# mainBoard_New_3-21_v10.net
KiCad netlist of a schematic drawn in EAGLE
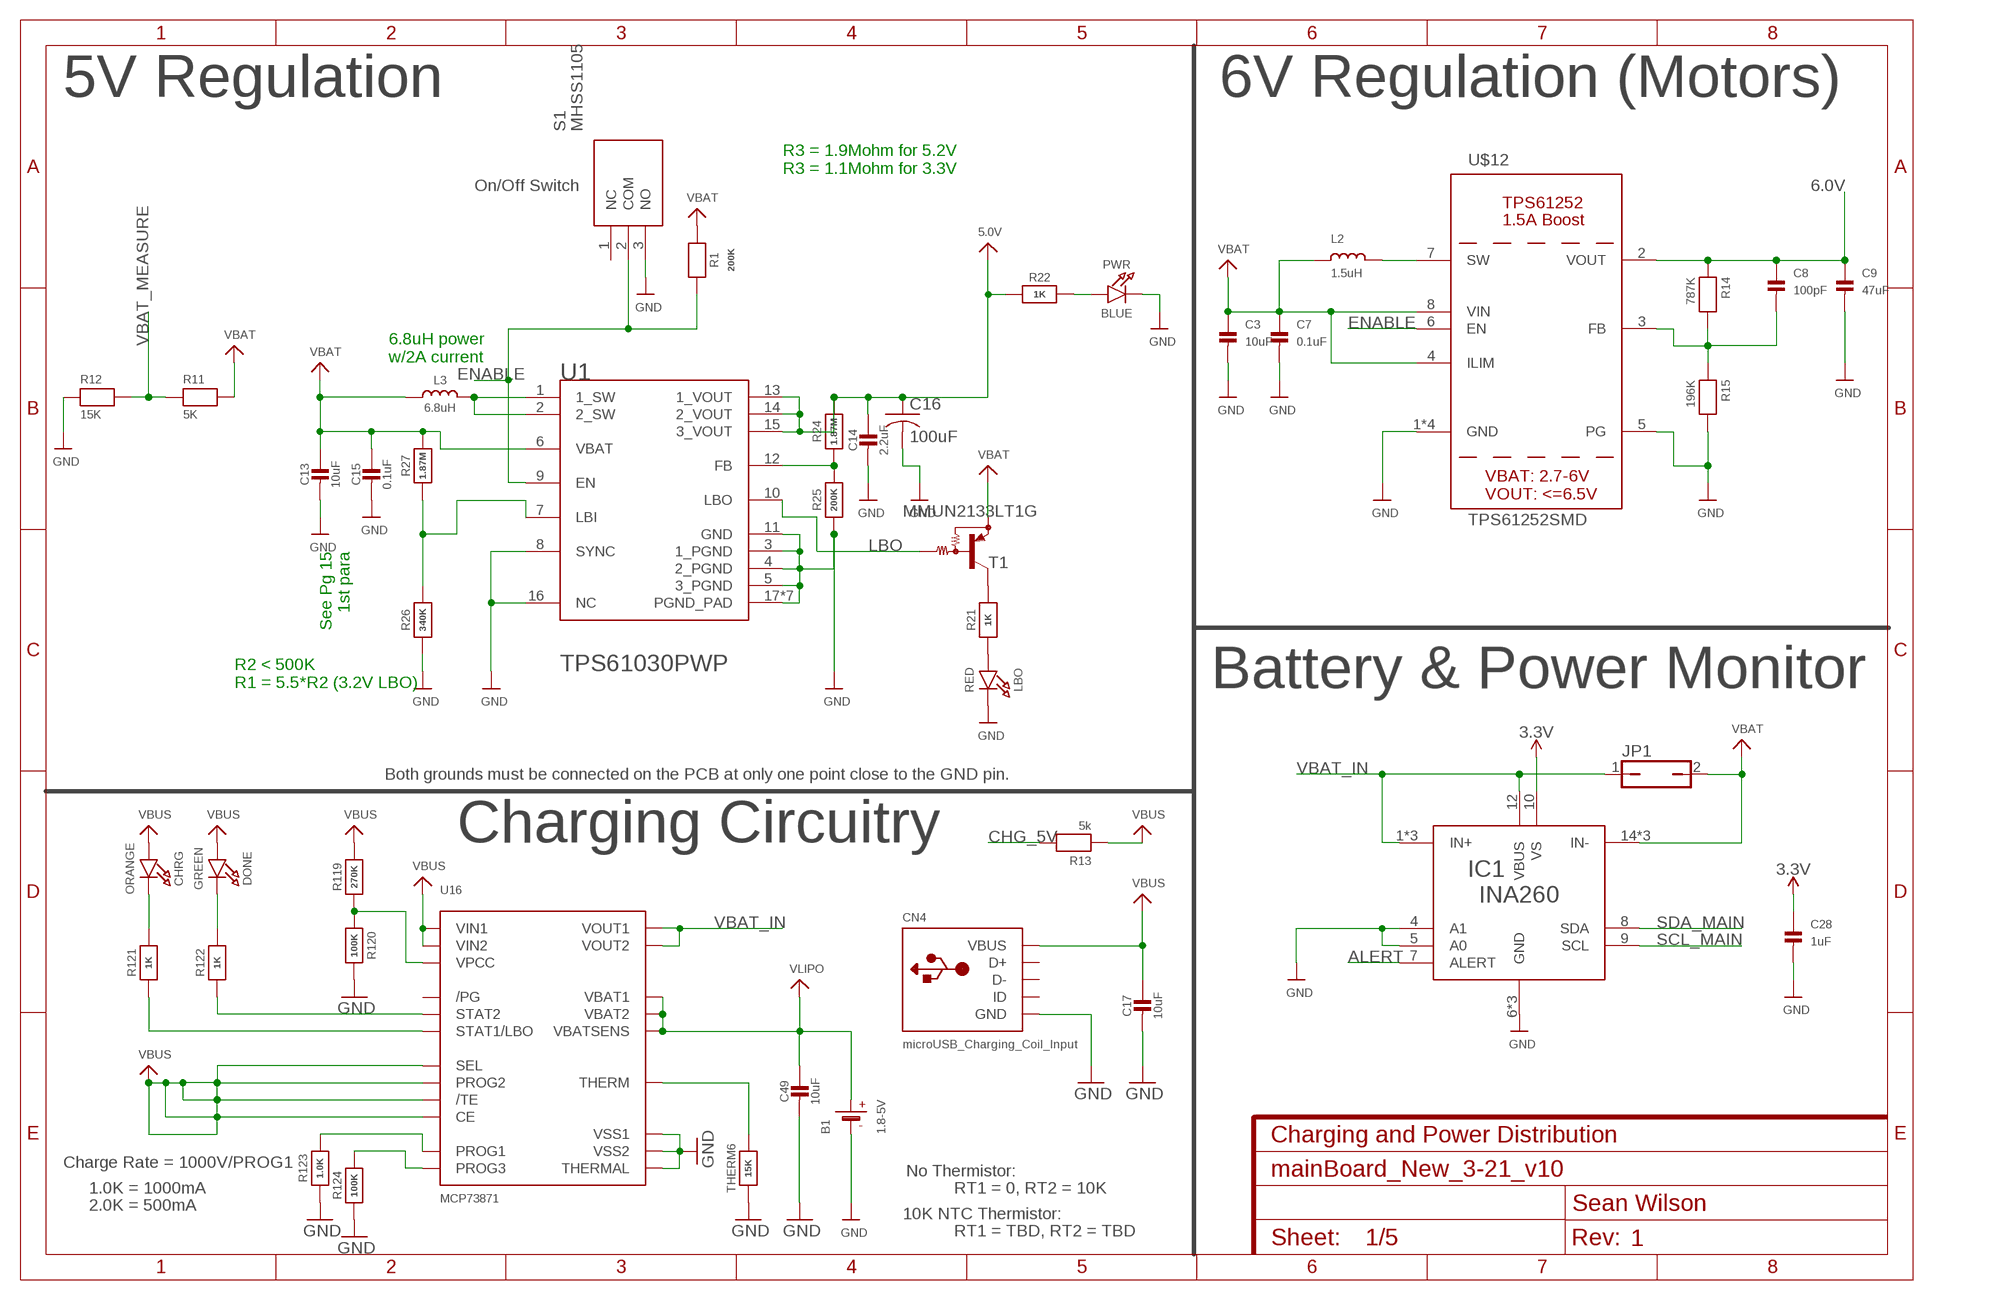
[diagram p0: schematic, sheet 1]
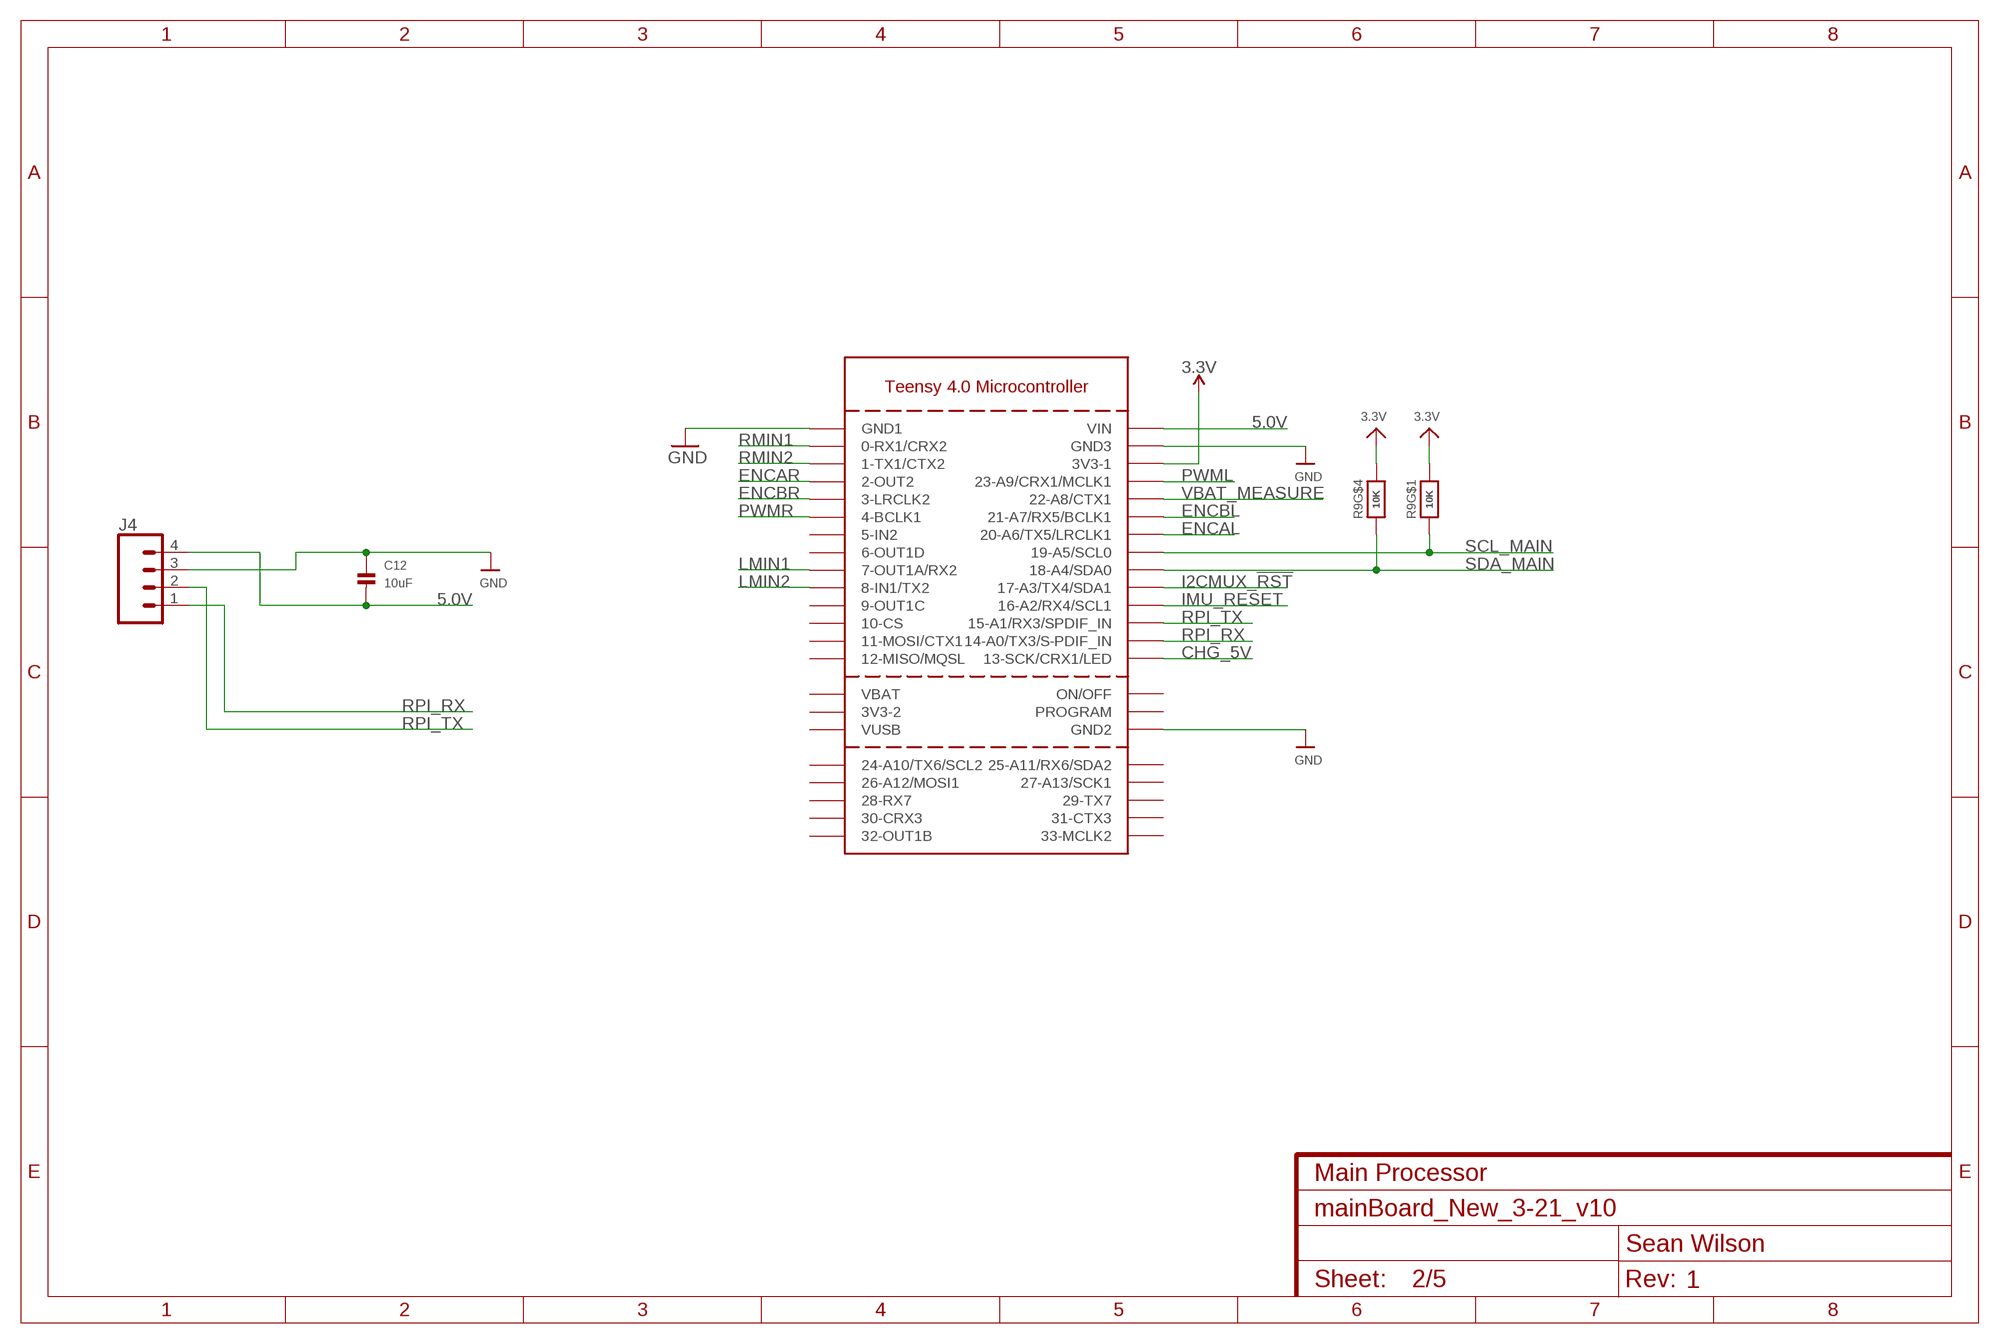
[diagram p1: schematic, sheet 2]
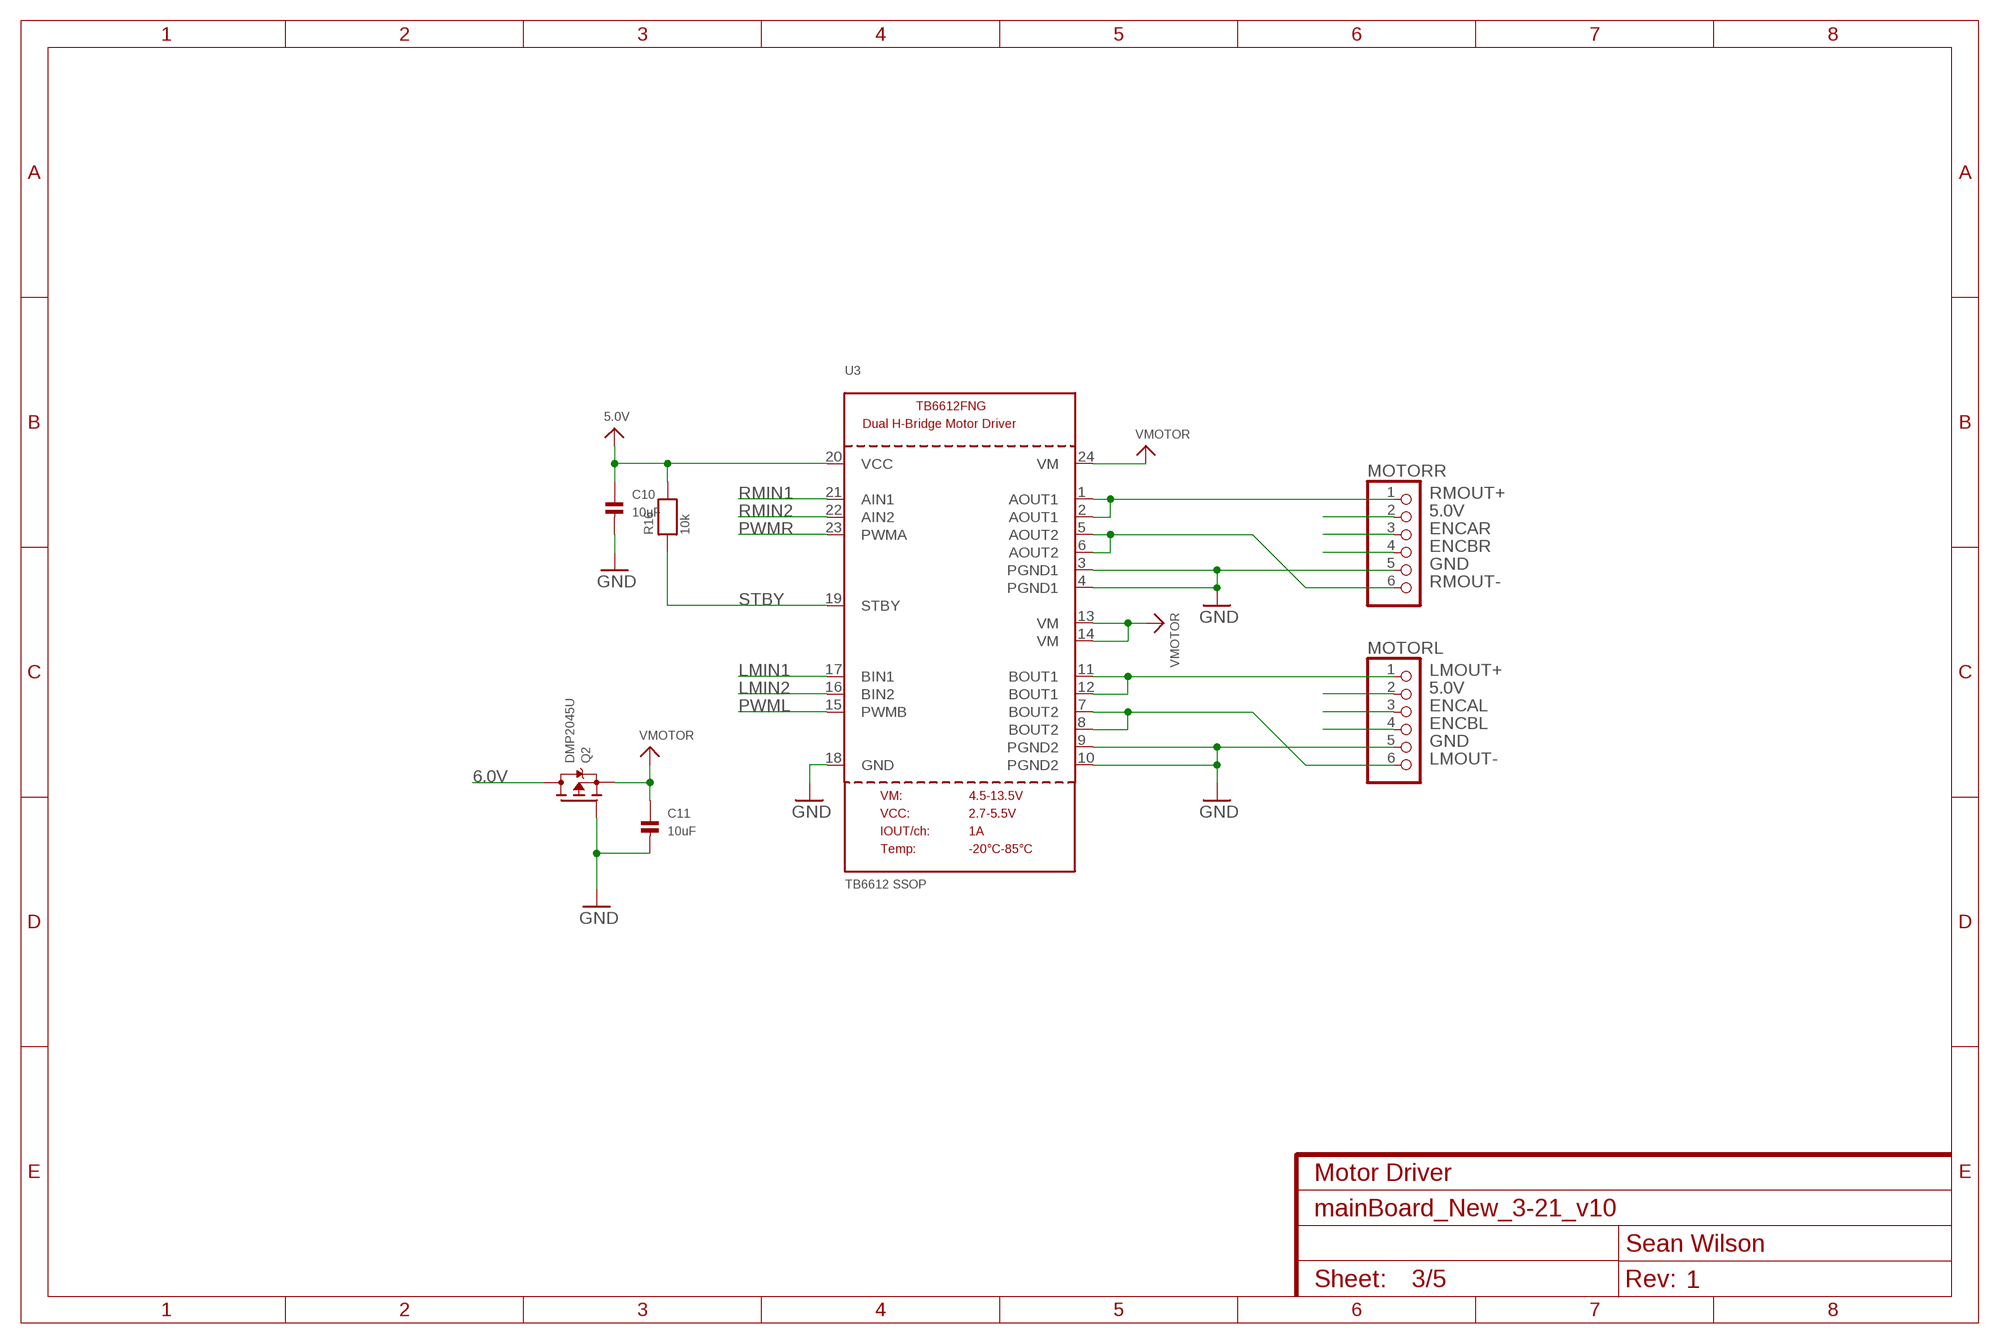
[diagram p2: schematic, sheet 3]
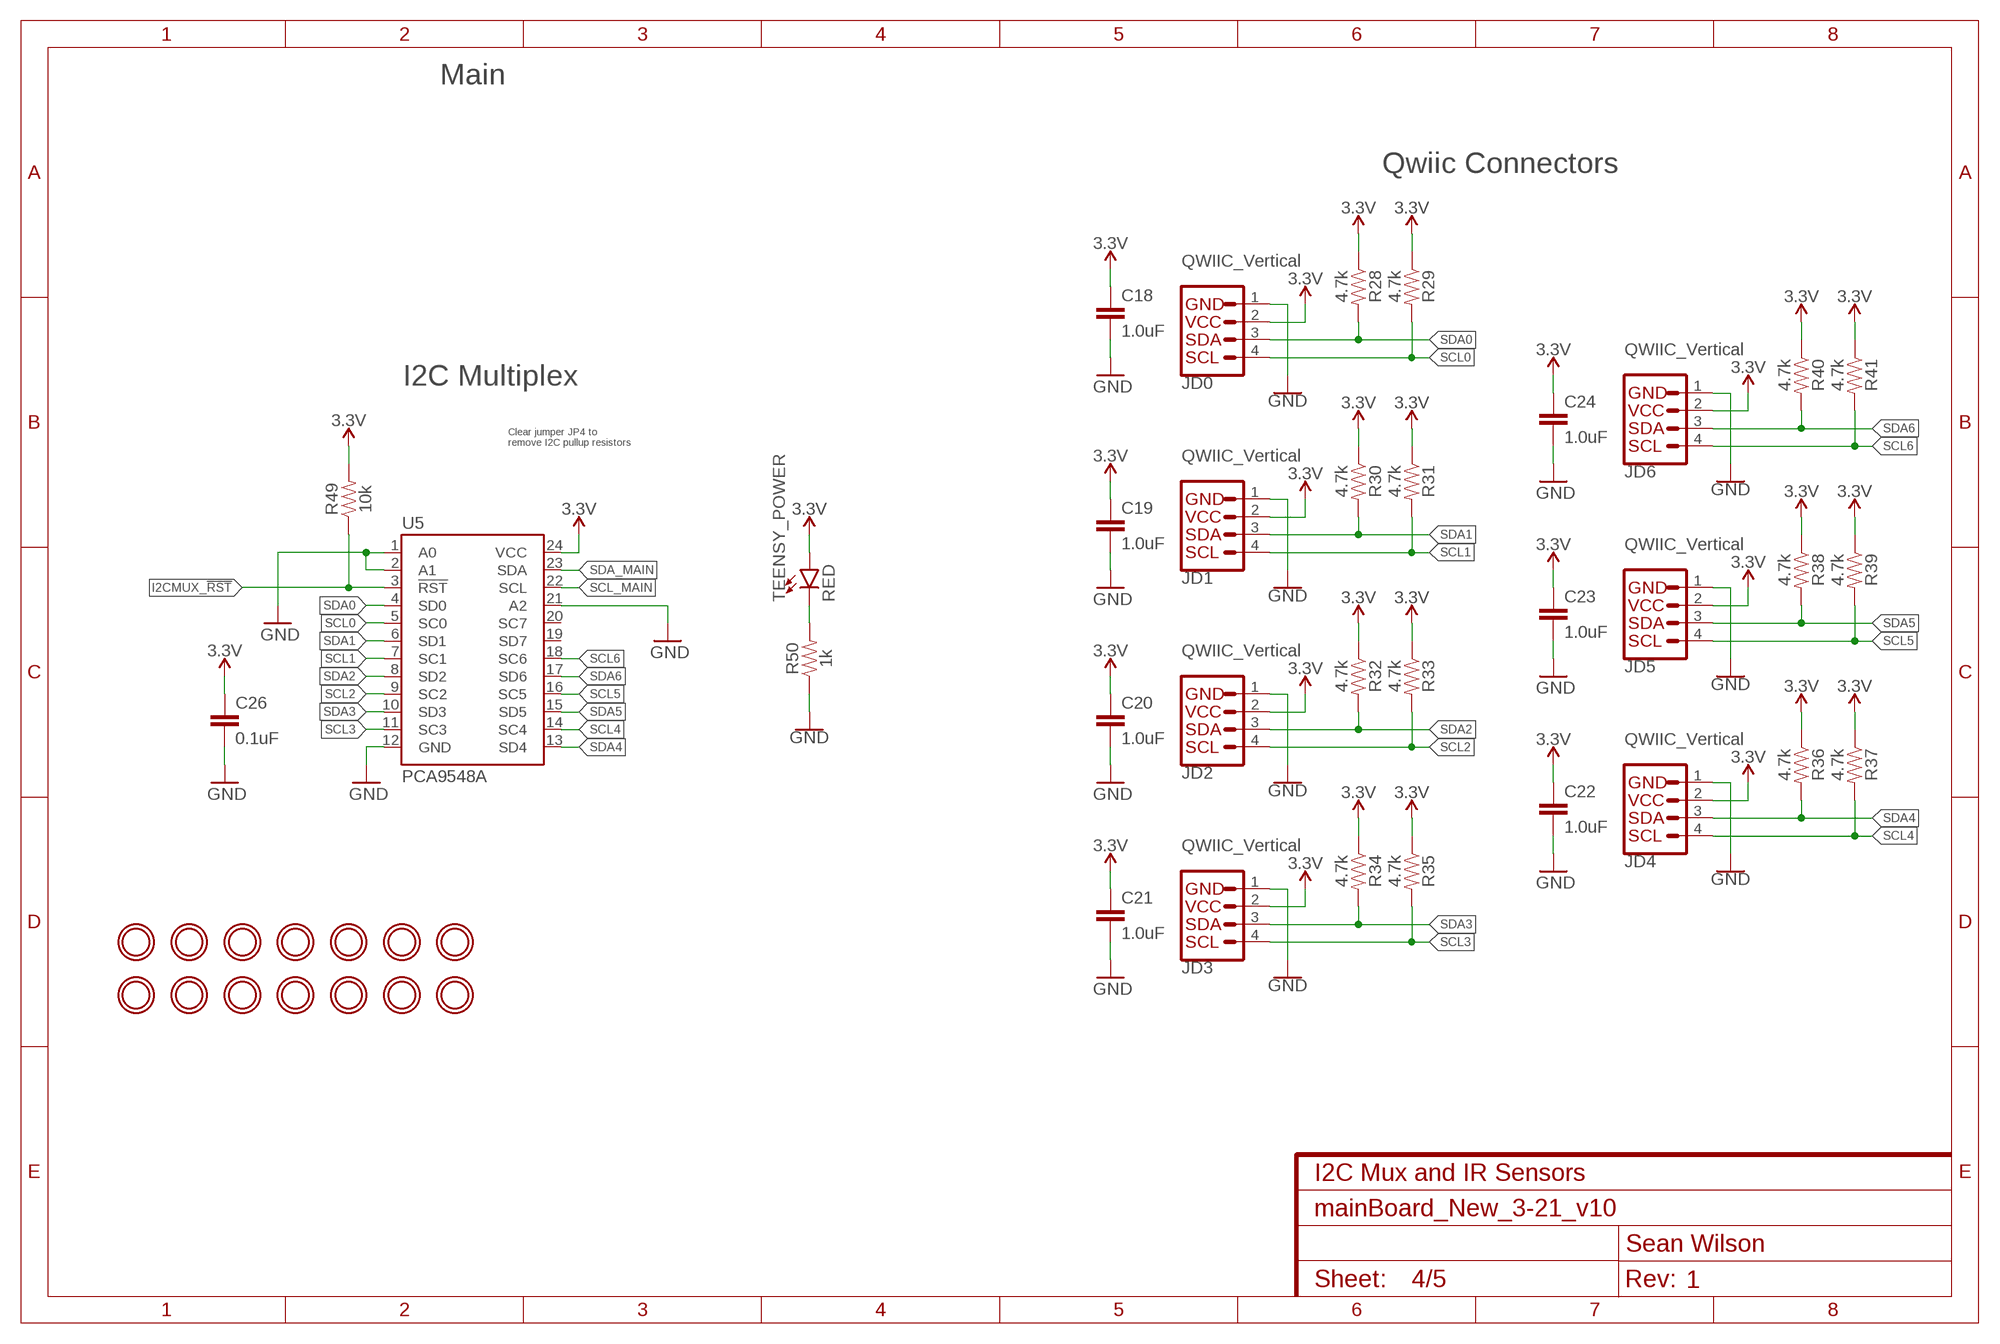
[diagram p3: schematic, sheet 4]
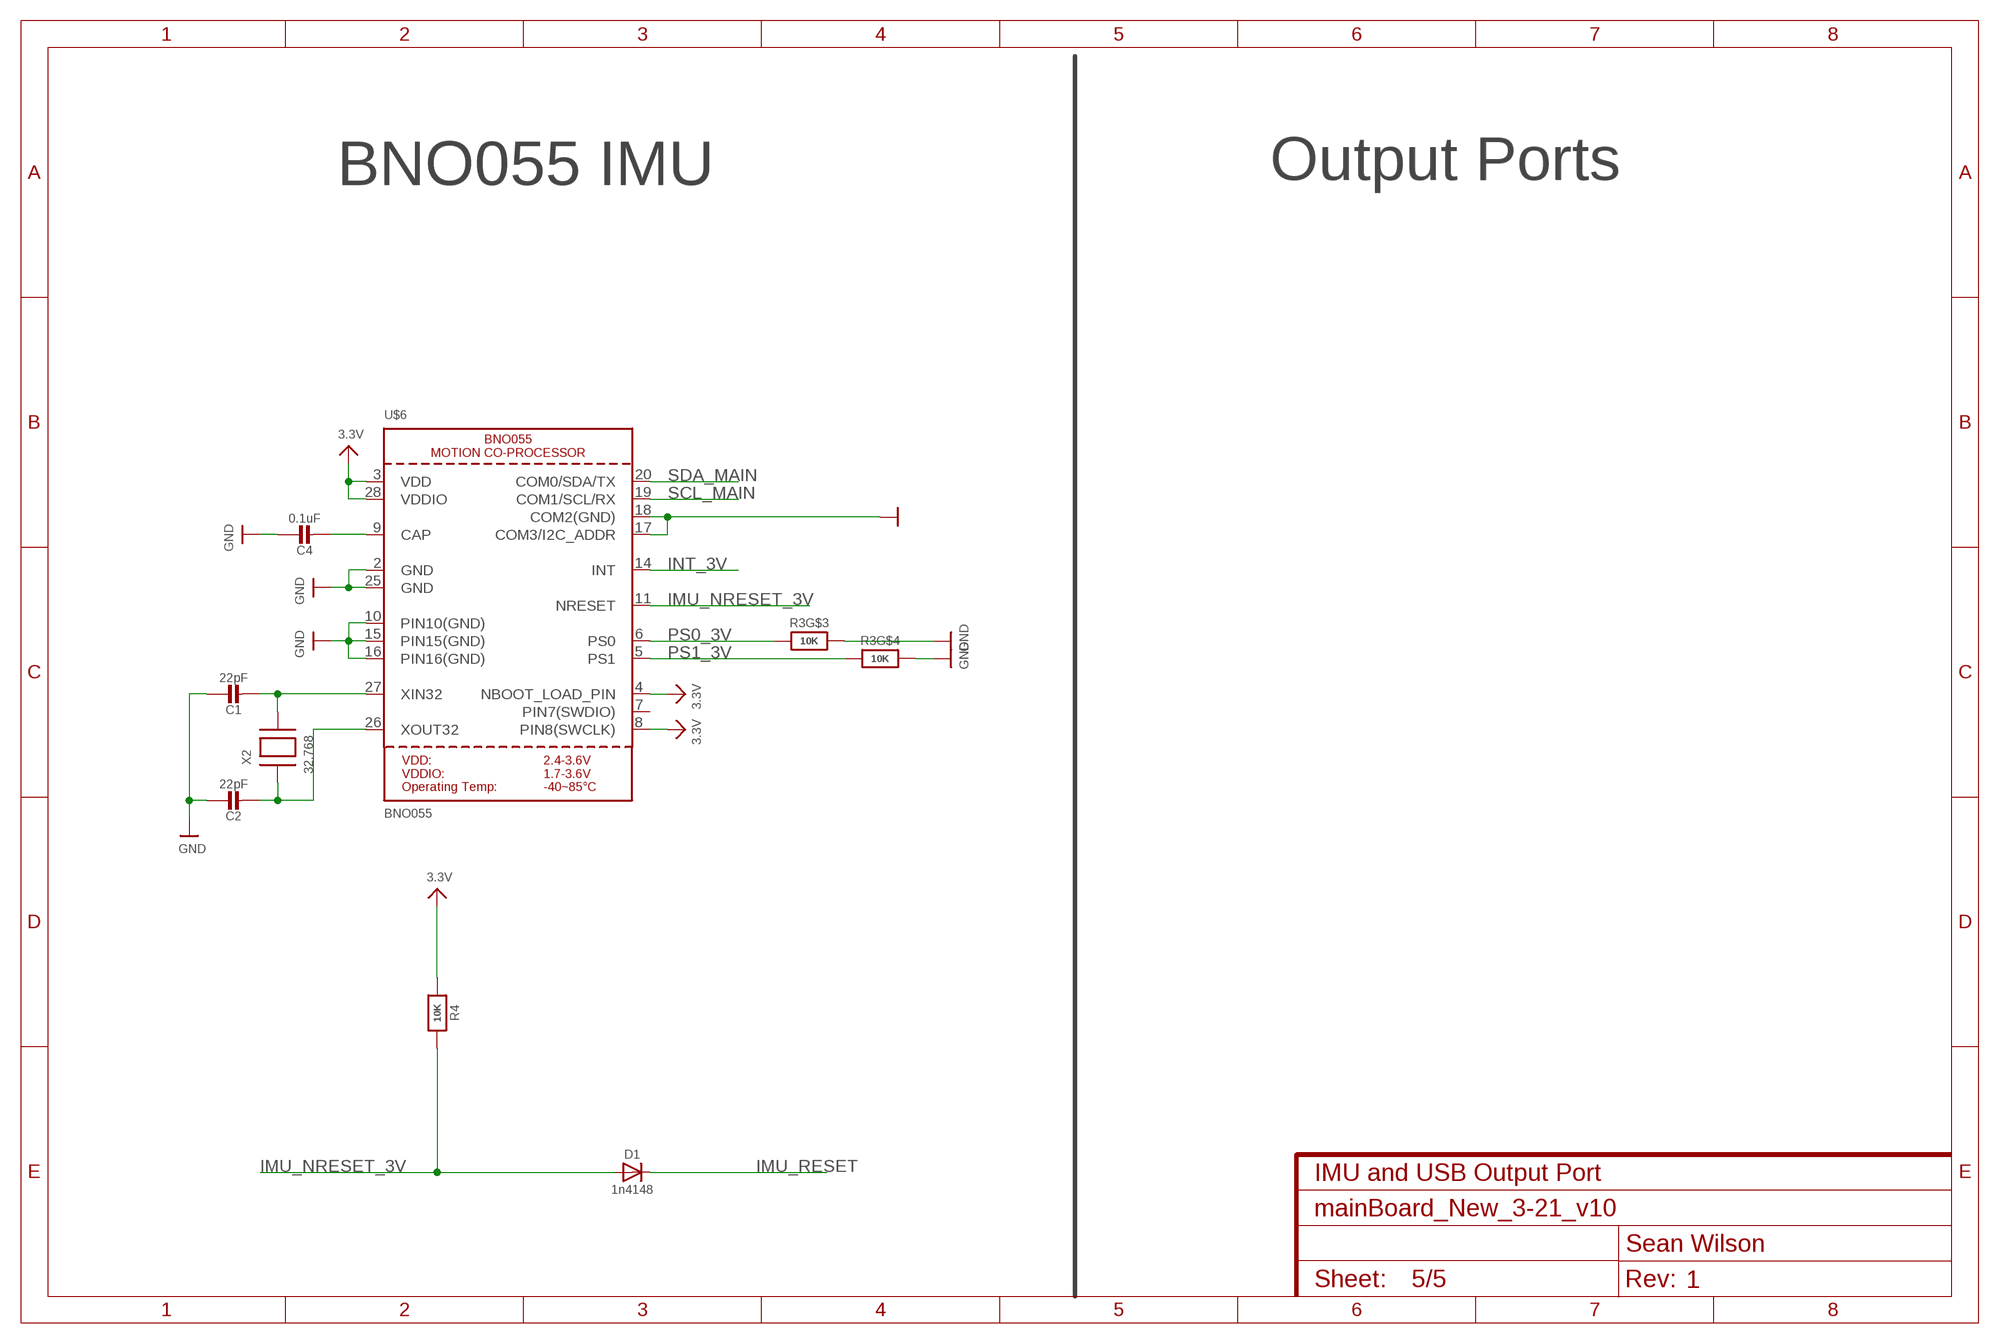
[diagram p4: schematic, sheet 5]

(export (version "E")
  (design (tool "Eeschema 10.0.6"))
  (components
    (comp (ref "C12")
      (value "10uF")
      (footprint "eagle-import:0603")
      (libsource (lib "eagle-import") (part "CAP_CERAMIC0603"))
    )
    (comp (ref "J4")
      (value "CONN_041X04_NO_SILK")
      (footprint "eagle-import:1X04_NO_SILK")
      (libsource (lib "eagle-import") (part "CONN_041X04_NO_SILK"))
    )
    (comp (ref "R9")
      (value "10K")
      (footprint "eagle-import:RESPACK_4X0603")
      (libsource (lib "eagle-import") (part "RESISTOR_4PACK"))
    )
    (comp (ref "U$57")
      (value "TEENSY40")
      (footprint "eagle-import:TEENSY40")
      (libsource (lib "eagle-import") (part "TEENSY40"))
    )
    (comp (ref "C10")
      (value "10uF")
      (footprint "eagle-import:0603")
      (libsource (lib "eagle-import") (part "CAP_CERAMIC0603"))
    )
    (comp (ref "C11")
      (value "10uF")
      (footprint "eagle-import:0603")
      (libsource (lib "eagle-import") (part "CAP_CERAMIC0603"))
    )
    (comp (ref "MOTORL")
      (value "PINHD-1X6CB")
      (footprint "eagle-import:1X06-CLEANBIG")
      (libsource (lib "eagle-import") (part "PINHD-1X6CB"))
    )
    (comp (ref "MOTORR")
      (value "PINHD-1X6CB")
      (footprint "eagle-import:1X06-CLEANBIG")
      (libsource (lib "eagle-import") (part "PINHD-1X6CB"))
    )
    (comp (ref "Q2")
      (value "DMP2045U")
      (footprint "eagle-import:SOT23-WIDE")
      (libsource (lib "eagle-import") (part "MOSFET-PWIDE"))
    )
    (comp (ref "R16")
      (value "10k")
      (footprint "eagle-import:0805")
      (libsource (lib "eagle-import") (part "RESISTOR0805"))
    )
    (comp (ref "U3")
      (value "TB6612 SSOP")
      (footprint "eagle-import:SSOP24")
      (libsource (lib "eagle-import") (part "TB6612FNGSSOP"))
    )
    (comp (ref "C1")
      (value "22pF")
      (footprint "eagle-import:0603-NO")
      (libsource (lib "eagle-import") (part "CAP_CERAMIC0603_NO"))
    )
    (comp (ref "C2")
      (value "22pF")
      (footprint "eagle-import:0603-NO")
      (libsource (lib "eagle-import") (part "CAP_CERAMIC0603_NO"))
    )
    (comp (ref "C4")
      (value "0.1uF")
      (footprint "eagle-import:0603-NO")
      (libsource (lib "eagle-import") (part "CAP_CERAMIC0603_NO"))
    )
    (comp (ref "D1")
      (value "1n4148")
      (footprint "eagle-import:SOD-323")
      (libsource (lib "eagle-import") (part "DIODESOD-323"))
    )
    (comp (ref "R3")
      (value "10K")
      (footprint "eagle-import:RESPACK_4X0603")
      (libsource (lib "eagle-import") (part "RESISTOR_4PACK"))
    )
    (comp (ref "R4")
      (value "10K")
      (footprint "eagle-import:0603-NO")
      (libsource (lib "eagle-import") (part "RESISTOR_0603_NOOUT"))
    )
    (comp (ref "U$6")
      (value "BNO055")
      (footprint "eagle-import:BNO055")
      (libsource (lib "eagle-import") (part "BNO055"))
    )
    (comp (ref "X2")
      (value "32.768")
      (footprint "eagle-import:XTAL3215")
      (libsource (lib "eagle-import") (part "XTAL-3.2X1.5"))
    )
    (comp (ref "C18")
      (value "1.0uF")
      (footprint "eagle-import:0603")
      (libsource (lib "eagle-import") (part "1.0UF-0603-16V-10%"))
    )
    (comp (ref "C19")
      (value "1.0uF")
      (footprint "eagle-import:0603")
      (libsource (lib "eagle-import") (part "1.0UF-0603-16V-10%"))
    )
    (comp (ref "C20")
      (value "1.0uF")
      (footprint "eagle-import:0603")
      (libsource (lib "eagle-import") (part "1.0UF-0603-16V-10%"))
    )
    (comp (ref "C21")
      (value "1.0uF")
      (footprint "eagle-import:0603")
      (libsource (lib "eagle-import") (part "1.0UF-0603-16V-10%"))
    )
    (comp (ref "C22")
      (value "1.0uF")
      (footprint "eagle-import:0603")
      (libsource (lib "eagle-import") (part "1.0UF-0603-16V-10%"))
    )
    (comp (ref "C23")
      (value "1.0uF")
      (footprint "eagle-import:0603")
      (libsource (lib "eagle-import") (part "1.0UF-0603-16V-10%"))
    )
    (comp (ref "C24")
      (value "1.0uF")
      (footprint "eagle-import:0603")
      (libsource (lib "eagle-import") (part "1.0UF-0603-16V-10%"))
    )
    (comp (ref "C26")
      (value "0.1uF")
      (footprint "eagle-import:0603")
      (libsource (lib "eagle-import") (part "0.1UF-0603-25V-(+80/-20%)"))
    )
    (comp (ref "JD0")
      (value "QWIIC_Vertical")
      (footprint "eagle-import:JST04_1MM_VERT")
      (libsource (lib "eagle-import") (part "QWIIC_CONNECTOR"))
    )
    (comp (ref "JD1")
      (value "QWIIC_Vertical")
      (footprint "eagle-import:JST04_1MM_VERT")
      (libsource (lib "eagle-import") (part "QWIIC_CONNECTOR"))
    )
    (comp (ref "JD2")
      (value "QWIIC_Vertical")
      (footprint "eagle-import:JST04_1MM_VERT")
      (libsource (lib "eagle-import") (part "QWIIC_CONNECTOR"))
    )
    (comp (ref "JD3")
      (value "QWIIC_Vertical")
      (footprint "eagle-import:JST04_1MM_VERT")
      (libsource (lib "eagle-import") (part "QWIIC_CONNECTOR"))
    )
    (comp (ref "JD4")
      (value "QWIIC_Vertical")
      (footprint "eagle-import:JST04_1MM_VERT")
      (libsource (lib "eagle-import") (part "QWIIC_CONNECTOR"))
    )
    (comp (ref "JD5")
      (value "QWIIC_Vertical")
      (footprint "eagle-import:JST04_1MM_VERT")
      (libsource (lib "eagle-import") (part "QWIIC_CONNECTOR"))
    )
    (comp (ref "JD6")
      (value "QWIIC_Vertical")
      (footprint "eagle-import:JST04_1MM_VERT")
      (libsource (lib "eagle-import") (part "QWIIC_CONNECTOR"))
    )
    (comp (ref "R28")
      (value "4.7k")
      (footprint "eagle-import:0603")
      (libsource (lib "eagle-import") (part "4.7KOHM-0603-1/10W-1%"))
    )
    (comp (ref "R29")
      (value "4.7k")
      (footprint "eagle-import:0603")
      (libsource (lib "eagle-import") (part "4.7KOHM-0603-1/10W-1%"))
    )
    (comp (ref "R30")
      (value "4.7k")
      (footprint "eagle-import:0603")
      (libsource (lib "eagle-import") (part "4.7KOHM-0603-1/10W-1%"))
    )
    (comp (ref "R31")
      (value "4.7k")
      (footprint "eagle-import:0603")
      (libsource (lib "eagle-import") (part "4.7KOHM-0603-1/10W-1%"))
    )
    (comp (ref "R32")
      (value "4.7k")
      (footprint "eagle-import:0603")
      (libsource (lib "eagle-import") (part "4.7KOHM-0603-1/10W-1%"))
    )
    (comp (ref "R33")
      (value "4.7k")
      (footprint "eagle-import:0603")
      (libsource (lib "eagle-import") (part "4.7KOHM-0603-1/10W-1%"))
    )
    (comp (ref "R34")
      (value "4.7k")
      (footprint "eagle-import:0603")
      (libsource (lib "eagle-import") (part "4.7KOHM-0603-1/10W-1%"))
    )
    (comp (ref "R35")
      (value "4.7k")
      (footprint "eagle-import:0603")
      (libsource (lib "eagle-import") (part "4.7KOHM-0603-1/10W-1%"))
    )
    (comp (ref "R36")
      (value "4.7k")
      (footprint "eagle-import:0603")
      (libsource (lib "eagle-import") (part "4.7KOHM-0603-1/10W-1%"))
    )
    (comp (ref "R37")
      (value "4.7k")
      (footprint "eagle-import:0603")
      (libsource (lib "eagle-import") (part "4.7KOHM-0603-1/10W-1%"))
    )
    (comp (ref "R38")
      (value "4.7k")
      (footprint "eagle-import:0603")
      (libsource (lib "eagle-import") (part "4.7KOHM-0603-1/10W-1%"))
    )
    (comp (ref "R39")
      (value "4.7k")
      (footprint "eagle-import:0603")
      (libsource (lib "eagle-import") (part "4.7KOHM-0603-1/10W-1%"))
    )
    (comp (ref "R40")
      (value "4.7k")
      (footprint "eagle-import:0603")
      (libsource (lib "eagle-import") (part "4.7KOHM-0603-1/10W-1%"))
    )
    (comp (ref "R41")
      (value "4.7k")
      (footprint "eagle-import:0603")
      (libsource (lib "eagle-import") (part "4.7KOHM-0603-1/10W-1%"))
    )
    (comp (ref "R49")
      (value "10k")
      (footprint "eagle-import:0603")
      (libsource (lib "eagle-import") (part "10KOHM-0603-1/10W-1%"))
    )
    (comp (ref "R50")
      (value "1k")
      (footprint "eagle-import:0603")
      (libsource (lib "eagle-import") (part "1KOHM-0603-1/10W-1%"))
    )
    (comp (ref "TEENSY_POWER")
      (value "RED")
      (footprint "eagle-import:LED-0603")
      (libsource (lib "eagle-import") (part "LED-RED0603"))
    )
    (comp (ref "U$8")
      (value "MOUNTINGHOLE2.5")
      (footprint "eagle-import:MOUNTINGHOLE_2.5_PLATED")
      (libsource (lib "eagle-import") (part "MOUNTINGHOLE2.5"))
    )
    (comp (ref "U$30")
      (value "MOUNTINGHOLE2.5")
      (footprint "eagle-import:MOUNTINGHOLE_2.5_PLATED")
      (libsource (lib "eagle-import") (part "MOUNTINGHOLE2.5"))
    )
    (comp (ref "U$31")
      (value "MOUNTINGHOLE2.5")
      (footprint "eagle-import:MOUNTINGHOLE_2.5_PLATED")
      (libsource (lib "eagle-import") (part "MOUNTINGHOLE2.5"))
    )
    (comp (ref "U$32")
      (value "MOUNTINGHOLE2.5")
      (footprint "eagle-import:MOUNTINGHOLE_2.5_PLATED")
      (libsource (lib "eagle-import") (part "MOUNTINGHOLE2.5"))
    )
    (comp (ref "U$33")
      (value "MOUNTINGHOLE2.5")
      (footprint "eagle-import:MOUNTINGHOLE_2.5_PLATED")
      (libsource (lib "eagle-import") (part "MOUNTINGHOLE2.5"))
    )
    (comp (ref "U$34")
      (value "MOUNTINGHOLE2.5")
      (footprint "eagle-import:MOUNTINGHOLE_2.5_PLATED")
      (libsource (lib "eagle-import") (part "MOUNTINGHOLE2.5"))
    )
    (comp (ref "U$35")
      (value "MOUNTINGHOLE2.5")
      (footprint "eagle-import:MOUNTINGHOLE_2.5_PLATED")
      (libsource (lib "eagle-import") (part "MOUNTINGHOLE2.5"))
    )
    (comp (ref "U$36")
      (value "MOUNTINGHOLE2.5")
      (footprint "eagle-import:MOUNTINGHOLE_2.5_PLATED")
      (libsource (lib "eagle-import") (part "MOUNTINGHOLE2.5"))
    )
    (comp (ref "U$37")
      (value "MOUNTINGHOLE2.5")
      (footprint "eagle-import:MOUNTINGHOLE_2.5_PLATED")
      (libsource (lib "eagle-import") (part "MOUNTINGHOLE2.5"))
    )
    (comp (ref "U$43")
      (value "MOUNTINGHOLE2.5")
      (footprint "eagle-import:MOUNTINGHOLE_2.5_PLATED")
      (libsource (lib "eagle-import") (part "MOUNTINGHOLE2.5"))
    )
    (comp (ref "U$45")
      (value "MOUNTINGHOLE2.5")
      (footprint "eagle-import:MOUNTINGHOLE_2.5_PLATED")
      (libsource (lib "eagle-import") (part "MOUNTINGHOLE2.5"))
    )
    (comp (ref "U$46")
      (value "MOUNTINGHOLE2.5")
      (footprint "eagle-import:MOUNTINGHOLE_2.5_PLATED")
      (libsource (lib "eagle-import") (part "MOUNTINGHOLE2.5"))
    )
    (comp (ref "U$47")
      (value "MOUNTINGHOLE2.5")
      (footprint "eagle-import:MOUNTINGHOLE_2.5_PLATED")
      (libsource (lib "eagle-import") (part "MOUNTINGHOLE2.5"))
    )
    (comp (ref "U$48")
      (value "MOUNTINGHOLE2.5")
      (footprint "eagle-import:MOUNTINGHOLE_2.5_PLATED")
      (libsource (lib "eagle-import") (part "MOUNTINGHOLE2.5"))
    )
    (comp (ref "U5")
      (value "PCA9548A")
      (footprint "eagle-import:TSSOP28")
      (libsource (lib "eagle-import") (part "PCA9548A"))
    )
    (comp (ref "B1")
      (value "1.8-5V")
      (footprint "eagle-import:JSTPH2")
      (libsource (lib "eagle-import") (part "BATTERY"))
    )
    (comp (ref "C3")
      (value "10uF")
      (footprint "eagle-import:0603")
      (libsource (lib "eagle-import") (part "CAP_CERAMIC0603"))
    )
    (comp (ref "C7")
      (value "0.1uF")
      (footprint "eagle-import:0805")
      (libsource (lib "eagle-import") (part "CAP_CERAMIC0805"))
    )
    (comp (ref "C8")
      (value "100pF")
      (footprint "eagle-import:0603")
      (libsource (lib "eagle-import") (part "CAP_CERAMIC0603"))
    )
    (comp (ref "C9")
      (value "47uF")
      (footprint "eagle-import:1206")
      (libsource (lib "eagle-import") (part "CAP_CERAMIC1206"))
    )
    (comp (ref "C13")
      (value "10uF")
      (footprint "eagle-import:0805-NO")
      (libsource (lib "eagle-import") (part "CAP_CERAMIC0805-NOOUTLINE"))
    )
    (comp (ref "C14")
      (value "2.2uF")
      (footprint "eagle-import:0805-NO")
      (libsource (lib "eagle-import") (part "CAP_CERAMIC0805-NOOUTLINE"))
    )
    (comp (ref "C15")
      (value "0.1uF")
      (footprint "eagle-import:0805_10MGAP")
      (libsource (lib "eagle-import") (part "CAP_CERAMIC0805_10MGAP"))
    )
    (comp (ref "C16")
      (value "100uF")
      (footprint "eagle-import:C1210")
      (libsource (lib "eagle-import") (part "C-USC1210"))
    )
    (comp (ref "C17")
      (value "10uF")
      (footprint "eagle-import:0805-NO")
      (libsource (lib "eagle-import") (part "CAP_CERAMIC0805-NOOUTLINE"))
    )
    (comp (ref "C28")
      (value "1uF")
      (footprint "eagle-import:0603-NO")
      (libsource (lib "eagle-import") (part "CAP_CERAMIC0603_NO"))
    )
    (comp (ref "C49")
      (value "10uF")
      (footprint "eagle-import:0805-NO")
      (libsource (lib "eagle-import") (part "CAP_CERAMIC0805-NOOUTLINE"))
    )
    (comp (ref "CHRG")
      (value "ORANGE")
      (footprint "eagle-import:CHIPLED_0805_NOOUTLINE")
      (libsource (lib "eagle-import") (part "LED0805_NOOUTLINE"))
    )
    (comp (ref "CN4")
      (value "microUSB_Charging_Coil_Input")
      (footprint "eagle-import:4UCONN_20329")
      (libsource (lib "eagle-import") (part "USBMICRO_20329"))
    )
    (comp (ref "DONE")
      (value "GREEN")
      (footprint "eagle-import:CHIPLED_0805_NOOUTLINE")
      (libsource (lib "eagle-import") (part "LED0805_NOOUTLINE"))
    )
    (comp (ref "IC1")
      (value "INA260")
      (footprint "eagle-import:TSSOP16")
      (libsource (lib "eagle-import") (part "INA260"))
    )
    (comp (ref "JP1")
      (value "JP1Q")
      (footprint "eagle-import:JP1")
      (libsource (lib "eagle-import") (part "JP1Q"))
    )
    (comp (ref "L2")
      (value "1.5uH")
      (footprint "eagle-import:MURATA_DFE252012P-1R5M=P2")
      (libsource (lib "eagle-import") (part "MURATA_DFE252012P-1R5M=P2"))
    )
    (comp (ref "L3")
      (value "6.8uH")
      (footprint "eagle-import:INDUCTOR_5X5MM_TDK_VLC5045")
      (libsource (lib "eagle-import") (part "INDUCTORTDK_VLC5045"))
    )
    (comp (ref "LBO")
      (value "RED")
      (footprint "eagle-import:CHIPLED_0805_NOOUTLINE")
      (libsource (lib "eagle-import") (part "LED0805_NOOUTLINE"))
    )
    (comp (ref "PWR")
      (value "BLUE")
      (footprint "eagle-import:CHIPLED_0805_NOOUTLINE")
      (libsource (lib "eagle-import") (part "LED0805_NOOUTLINE"))
    )
    (comp (ref "R1")
      (value "200K")
      (footprint "eagle-import:0805-NO")
      (libsource (lib "eagle-import") (part "RESISTOR0805_NOOUTLINE"))
    )
    (comp (ref "R11")
      (value "5K")
      (footprint "eagle-import:0805")
      (libsource (lib "eagle-import") (part "RESISTOR0805"))
    )
    (comp (ref "R12")
      (value "15K")
      (footprint "eagle-import:0805")
      (libsource (lib "eagle-import") (part "RESISTOR0805"))
    )
    (comp (ref "R13")
      (value "5k")
      (footprint "eagle-import:0805")
      (libsource (lib "eagle-import") (part "RESISTOR0805"))
    )
    (comp (ref "R14")
      (value "787K")
      (footprint "eagle-import:0805")
      (libsource (lib "eagle-import") (part "RESISTOR0805"))
    )
    (comp (ref "R15")
      (value "196K")
      (footprint "eagle-import:0805")
      (libsource (lib "eagle-import") (part "RESISTOR0805"))
    )
    (comp (ref "R21")
      (value "1K")
      (footprint "eagle-import:0805-NO")
      (libsource (lib "eagle-import") (part "RESISTOR0805_NOOUTLINE"))
    )
    (comp (ref "R22")
      (value "1K")
      (footprint "eagle-import:0805-NO")
      (libsource (lib "eagle-import") (part "RESISTOR0805_NOOUTLINE"))
    )
    (comp (ref "R24")
      (value "1.87M")
      (footprint "eagle-import:0805-NO")
      (libsource (lib "eagle-import") (part "RESISTOR0805_NOOUTLINE"))
    )
    (comp (ref "R25")
      (value "200K")
      (footprint "eagle-import:0805-NO")
      (libsource (lib "eagle-import") (part "RESISTOR0805_NOOUTLINE"))
    )
    (comp (ref "R26")
      (value "340K")
      (footprint "eagle-import:_0805MP")
      (libsource (lib "eagle-import") (part "microbuilder_vf.jQhFfLl6SwyupizEU6PNDA_RESISTOR_0805MP"))
    )
    (comp (ref "R27")
      (value "1.87M")
      (footprint "eagle-import:_0805MP")
      (libsource (lib "eagle-import") (part "microbuilder_vf.jQhFfLl6SwyupizEU6PNDA_RESISTOR_0805MP"))
    )
    (comp (ref "R119")
      (value "270K")
      (footprint "eagle-import:0805-NO")
      (libsource (lib "eagle-import") (part "RESISTOR0805_NOOUTLINE"))
    )
    (comp (ref "R120")
      (value "100K")
      (footprint "eagle-import:0805-NO")
      (libsource (lib "eagle-import") (part "RESISTOR0805_NOOUTLINE"))
    )
    (comp (ref "R121")
      (value "1K")
      (footprint "eagle-import:0805-NO")
      (libsource (lib "eagle-import") (part "RESISTOR0805_NOOUTLINE"))
    )
    (comp (ref "R122")
      (value "1K")
      (footprint "eagle-import:0805-NO")
      (libsource (lib "eagle-import") (part "RESISTOR0805_NOOUTLINE"))
    )
    (comp (ref "R123")
      (value "1.0K")
      (footprint "eagle-import:0805-NO")
      (libsource (lib "eagle-import") (part "RESISTOR0805_NOOUTLINE"))
    )
    (comp (ref "R124")
      (value "100K")
      (footprint "eagle-import:0805-NO")
      (libsource (lib "eagle-import") (part "RESISTOR0805_NOOUTLINE"))
    )
    (comp (ref "S1")
      (value "MHSS1105")
      (footprint "eagle-import:MHSS1105")
      (fields (field (name "MOUSER_PART_NUMBER") "642-MHSS1105"))
      (libsource (lib "eagle-import") (part "MHSS1105"))
    )
    (comp (ref "T1")
      (value "MMUN2133LT1G")
      (footprint "eagle-import:SC59-BEC")
      (libsource (lib "eagle-import") (part "-PNP_DRIVER-SC59-BECMUN2114T1"))
    )
    (comp (ref "THERM6")
      (value "15K")
      (footprint "eagle-import:0805-NO")
      (libsource (lib "eagle-import") (part "RESISTOR0805_NOOUTLINE"))
    )
    (comp (ref "U$12")
      (value "TPS61252SMD")
      (footprint "eagle-import:TPS61252")
      (libsource (lib "eagle-import") (part "TPS61252SMD"))
    )
    (comp (ref "U1")
      (value "TEXAS_INSTRUMENTS_TPS61030PWPTEXAS_INSTRUMENTS_TPS61030PWP_0_0")
      (footprint "eagle-import:TEXAS_INSTRUMENTS_TPS61030PWP_0")
      (fields
        (field (name "DIGIKEY_PART_NUMBER") "296-27006-5-ND")
        (field (name "MF") "Texas Instruments")
        (field (name "MOUSER_PART_NUMBER") "595-TPS61030PWP")
      )
      (libsource (lib "eagle-import") (part "TEXAS_INSTRUMENTS_TPS61030PWPTEXAS_INSTRUMENTS_TPS61030PWP_0_0"))
    )
    (comp (ref "U16")
      (value "MCP73871")
      (footprint "eagle-import:QFN20_4MM")
      (libsource (lib "eagle-import") (part "MCP73871"))
    )
  )
  (nets
    (net (code "1") (name "3.3V") (class "Default")
      (node (ref "C18") (pin "1") (pinfunction "1_1") (pintype "passive"))
      (node (ref "C19") (pin "1") (pinfunction "1_1") (pintype "passive"))
      (node (ref "C20") (pin "1") (pinfunction "1_1") (pintype "passive"))
      (node (ref "C21") (pin "1") (pinfunction "1_1") (pintype "passive"))
      (node (ref "C22") (pin "1") (pinfunction "1_1") (pintype "passive"))
      (node (ref "C23") (pin "1") (pinfunction "1_1") (pintype "passive"))
      (node (ref "C24") (pin "1") (pinfunction "1_1") (pintype "passive"))
      (node (ref "C26") (pin "1") (pinfunction "1_1") (pintype "passive"))
      (node (ref "C28") (pin "1") (pinfunction "1_1") (pintype "passive"))
      (node (ref "IC1") (pin "10") (pinfunction "VS_10") (pintype "power_in"))
      (node (ref "JD0") (pin "2") (pinfunction "2_2") (pintype "power_in"))
      (node (ref "JD1") (pin "2") (pinfunction "2_2") (pintype "power_in"))
      (node (ref "JD2") (pin "2") (pinfunction "2_2") (pintype "power_in"))
      (node (ref "JD3") (pin "2") (pinfunction "2_2") (pintype "power_in"))
      (node (ref "JD4") (pin "2") (pinfunction "2_2") (pintype "power_in"))
      (node (ref "JD5") (pin "2") (pinfunction "2_2") (pintype "power_in"))
      (node (ref "JD6") (pin "2") (pinfunction "2_2") (pintype "power_in"))
      (node (ref "R28") (pin "1") (pinfunction "1_1") (pintype "passive"))
      (node (ref "R29") (pin "1") (pinfunction "1_1") (pintype "passive"))
      (node (ref "R30") (pin "1") (pinfunction "1_1") (pintype "passive"))
      (node (ref "R31") (pin "1") (pinfunction "1_1") (pintype "passive"))
      (node (ref "R32") (pin "1") (pinfunction "1_1") (pintype "passive"))
      (node (ref "R33") (pin "1") (pinfunction "1_1") (pintype "passive"))
      (node (ref "R34") (pin "1") (pinfunction "1_1") (pintype "passive"))
      (node (ref "R35") (pin "1") (pinfunction "1_1") (pintype "passive"))
      (node (ref "R36") (pin "1") (pinfunction "1_1") (pintype "passive"))
      (node (ref "R37") (pin "1") (pinfunction "1_1") (pintype "passive"))
      (node (ref "R38") (pin "1") (pinfunction "1_1") (pintype "passive"))
      (node (ref "R39") (pin "1") (pinfunction "1_1") (pintype "passive"))
      (node (ref "R4") (pin "1") (pinfunction "1_1") (pintype "passive"))
      (node (ref "R40") (pin "1") (pinfunction "1_1") (pintype "passive"))
      (node (ref "R41") (pin "1") (pinfunction "1_1") (pintype "passive"))
      (node (ref "R49") (pin "2") (pinfunction "2_2") (pintype "passive"))
      (node (ref "R9") (pin "1") (pinfunction "1_1") (pintype "passive"))
      (node (ref "R9") (pin "4") (pinfunction "1_4") (pintype "passive"))
      (node (ref "TEENSY_POWER") (pin "A") (pinfunction "A_A") (pintype "passive"))
      (node (ref "U$57") (pin "3V3-1") (pinfunction "3V3-1_3V3-1") (pintype "bidirectional"))
      (node (ref "U$6") (pin "28") (pinfunction "VDDIO_28") (pintype "power_in"))
      (node (ref "U$6") (pin "3") (pinfunction "VDD_3") (pintype "power_in"))
      (node (ref "U$6") (pin "4") (pinfunction "NBOOT_LOAD_PIN_4") (pintype "bidirectional"))
      (node (ref "U$6") (pin "8") (pinfunction "PIN8(SWCLK)_8") (pintype "bidirectional"))
      (node (ref "U5") (pin "24") (pinfunction "VCC_24") (pintype "bidirectional"))
    )
    (net (code "2") (name "5.0V") (class "Default")
      (node (ref "C10") (pin "1") (pinfunction "P$1_1") (pintype "passive"))
      (node (ref "C12") (pin "2") (pinfunction "P$2_2") (pintype "passive"))
      (node (ref "C14") (pin "1") (pinfunction "1_1") (pintype "passive"))
      (node (ref "C16") (pin "1") (pinfunction "1_1") (pintype "passive"))
      (node (ref "J4") (pin "4") (pinfunction "4_4") (pintype "passive"))
      (node (ref "MOTORL") (pin "2") (pinfunction "2_2") (pintype "passive"))
      (node (ref "MOTORR") (pin "2") (pinfunction "2_2") (pintype "passive"))
      (node (ref "R16") (pin "2") (pinfunction "2_2") (pintype "passive"))
      (node (ref "R22") (pin "1") (pinfunction "1_1") (pintype "passive"))
      (node (ref "R24") (pin "2") (pinfunction "2_2") (pintype "passive"))
      (node (ref "U$57") (pin "VIN") (pinfunction "VIN_VIN") (pintype "bidirectional"))
      (node (ref "U1") (pin "13") (pinfunction "1_VOUT_13") (pintype "bidirectional"))
      (node (ref "U1") (pin "14") (pinfunction "2_VOUT_14") (pintype "bidirectional"))
      (node (ref "U1") (pin "15") (pinfunction "3_VOUT_15") (pintype "bidirectional"))
      (node (ref "U3") (pin "20") (pinfunction "VCC_20") (pintype "power_in"))
    )
    (net (code "3") (name "6.0V") (class "Default")
      (node (ref "C8") (pin "1") (pinfunction "P$1_1") (pintype "passive"))
      (node (ref "C9") (pin "1") (pinfunction "P$1_1") (pintype "passive"))
      (node (ref "Q2") (pin "3") (pinfunction "D_3") (pintype "passive"))
      (node (ref "R14") (pin "1") (pinfunction "1_1") (pintype "passive"))
      (node (ref "U$12") (pin "2") (pinfunction "VOUT_2") (pintype "bidirectional"))
    )
    (net (code "4") (name "ALERT") (class "Default")
      (node (ref "IC1") (pin "7") (pinfunction "ALERT_7") (pintype "output"))
    )
    (net (code "5") (name "CHG_5V") (class "Default")
      (node (ref "R13") (pin "2") (pinfunction "2_2") (pintype "passive"))
      (node (ref "U$57") (pin "13-SCK/CRX1/LED") (pinfunction "13-SCK/CRX1/LED_13-SCK/CRX1/LED") (pintype "bidirectional"))
    )
    (net (code "6") (name "ENABLE") (class "Default")
      (node (ref "R1") (pin "2") (pinfunction "2_2") (pintype "passive"))
      (node (ref "S1") (pin "2") (pinfunction "COM_2") (pintype "bidirectional"))
      (node (ref "U$12") (pin "6") (pinfunction "EN_6") (pintype "bidirectional"))
      (node (ref "U1") (pin "9") (pinfunction "EN_9") (pintype "bidirectional"))
    )
    (net (code "7") (name "ENCAL") (class "Default")
      (node (ref "MOTORL") (pin "3") (pinfunction "3_3") (pintype "passive"))
      (node (ref "U$57") (pin "20-A6/TX5/LRCLK1") (pinfunction "20-A6/TX5/LRCLK1_20-A6/TX5/LRCLK1") (pintype "bidirectional"))
    )
    (net (code "8") (name "ENCAR") (class "Default")
      (node (ref "MOTORR") (pin "3") (pinfunction "3_3") (pintype "passive"))
      (node (ref "U$57") (pin "2-OUT2") (pinfunction "2-OUT2_2-OUT2") (pintype "bidirectional"))
    )
    (net (code "9") (name "ENCBL") (class "Default")
      (node (ref "MOTORL") (pin "4") (pinfunction "4_4") (pintype "passive"))
      (node (ref "U$57") (pin "21-A7/RX5/BCLK1") (pinfunction "21-A7/RX5/BCLK1_21-A7/RX5/BCLK1") (pintype "bidirectional"))
    )
    (net (code "10") (name "ENCBR") (class "Default")
      (node (ref "MOTORR") (pin "4") (pinfunction "4_4") (pintype "passive"))
      (node (ref "U$57") (pin "3-LRCLK2") (pinfunction "3-LRCLK2_3-LRCLK2") (pintype "bidirectional"))
    )
    (net (code "11") (name "GND") (class "Default")
      (node (ref "B1") (pin "1") (pinfunction "-_1") (pintype "passive"))
      (node (ref "C1") (pin "1") (pinfunction "1_1") (pintype "passive"))
      (node (ref "C10") (pin "2") (pinfunction "P$2_2") (pintype "passive"))
      (node (ref "C11") (pin "2") (pinfunction "P$2_2") (pintype "passive"))
      (node (ref "C12") (pin "1") (pinfunction "P$1_1") (pintype "passive"))
      (node (ref "C13") (pin "2") (pinfunction "2_2") (pintype "passive"))
      (node (ref "C14") (pin "2") (pinfunction "2_2") (pintype "passive"))
      (node (ref "C15") (pin "2") (pinfunction "2_2") (pintype "passive"))
      (node (ref "C16") (pin "2") (pinfunction "2_2") (pintype "passive"))
      (node (ref "C17") (pin "2") (pinfunction "2_2") (pintype "passive"))
      (node (ref "C18") (pin "2") (pinfunction "2_2") (pintype "passive"))
      (node (ref "C19") (pin "2") (pinfunction "2_2") (pintype "passive"))
      (node (ref "C2") (pin "1") (pinfunction "1_1") (pintype "passive"))
      (node (ref "C20") (pin "2") (pinfunction "2_2") (pintype "passive"))
      (node (ref "C21") (pin "2") (pinfunction "2_2") (pintype "passive"))
      (node (ref "C22") (pin "2") (pinfunction "2_2") (pintype "passive"))
      (node (ref "C23") (pin "2") (pinfunction "2_2") (pintype "passive"))
      (node (ref "C24") (pin "2") (pinfunction "2_2") (pintype "passive"))
      (node (ref "C26") (pin "2") (pinfunction "2_2") (pintype "passive"))
      (node (ref "C28") (pin "2") (pinfunction "2_2") (pintype "passive"))
      (node (ref "C3") (pin "2") (pinfunction "P$2_2") (pintype "passive"))
      (node (ref "C4") (pin "1") (pinfunction "1_1") (pintype "passive"))
      (node (ref "C49") (pin "2") (pinfunction "2_2") (pintype "passive"))
      (node (ref "C7") (pin "2") (pinfunction "P$2_2") (pintype "passive"))
      (node (ref "C9") (pin "2") (pinfunction "P$2_2") (pintype "passive"))
      (node (ref "CN4") (pin "BASE@1") (pinfunction "GND_BASE@1") (pintype "power_in"))
      (node (ref "CN4") (pin "BASE@2") (pinfunction "GND_BASE@2") (pintype "power_in"))
      (node (ref "CN4") (pin "GND") (pinfunction "GND_GND") (pintype "power_in"))
      (node (ref "CN4") (pin "SPRT@1") (pinfunction "GND_SPRT@1") (pintype "power_in"))
      (node (ref "CN4") (pin "SPRT@2") (pinfunction "GND_SPRT@2") (pintype "power_in"))
      (node (ref "CN4") (pin "SPRT@3") (pinfunction "GND_SPRT@3") (pintype "power_in"))
      (node (ref "CN4") (pin "SPRT@4") (pinfunction "GND_SPRT@4") (pintype "power_in"))
      (node (ref "IC1") (pin "11") (pinfunction "GND_11") (pintype "power_in"))
      (node (ref "IC1") (pin "13") (pinfunction "GND_13") (pintype "power_in"))
      (node (ref "IC1") (pin "4") (pinfunction "A1_4") (pintype "input"))
      (node (ref "IC1") (pin "5") (pinfunction "A0_5") (pintype "input"))
      (node (ref "IC1") (pin "6") (pinfunction "GND_6") (pintype "power_in"))
      (node (ref "J4") (pin "3") (pinfunction "3_3") (pintype "passive"))
      (node (ref "JD0") (pin "1") (pinfunction "1_1") (pintype "power_in"))
      (node (ref "JD1") (pin "1") (pinfunction "1_1") (pintype "power_in"))
      (node (ref "JD2") (pin "1") (pinfunction "1_1") (pintype "power_in"))
      (node (ref "JD3") (pin "1") (pinfunction "1_1") (pintype "power_in"))
      (node (ref "JD4") (pin "1") (pinfunction "1_1") (pintype "power_in"))
      (node (ref "JD5") (pin "1") (pinfunction "1_1") (pintype "power_in"))
      (node (ref "JD6") (pin "1") (pinfunction "1_1") (pintype "power_in"))
      (node (ref "LBO") (pin "C") (pinfunction "C_C") (pintype "passive"))
      (node (ref "MOTORL") (pin "5") (pinfunction "5_5") (pintype "passive"))
      (node (ref "MOTORR") (pin "5") (pinfunction "5_5") (pintype "passive"))
      (node (ref "PWR") (pin "C") (pinfunction "C_C") (pintype "passive"))
      (node (ref "Q2") (pin "1") (pinfunction "G_1") (pintype "passive"))
      (node (ref "R12") (pin "1") (pinfunction "1_1") (pintype "passive"))
      (node (ref "R120") (pin "2") (pinfunction "2_2") (pintype "passive"))
      (node (ref "R123") (pin "1") (pinfunction "1_1") (pintype "passive"))
      (node (ref "R124") (pin "1") (pinfunction "1_1") (pintype "passive"))
      (node (ref "R15") (pin "2") (pinfunction "2_2") (pintype "passive"))
      (node (ref "R25") (pin "1") (pinfunction "1_1") (pintype "passive"))
      (node (ref "R26") (pin "1") (pinfunction "1_1") (pintype "passive"))
      (node (ref "R3") (pin "5") (pinfunction "2_5") (pintype "passive"))
      (node (ref "R3") (pin "6") (pinfunction "2_6") (pintype "passive"))
      (node (ref "R50") (pin "1") (pinfunction "1_1") (pintype "passive"))
      (node (ref "S1") (pin "3") (pinfunction "NO_3") (pintype "bidirectional"))
      (node (ref "THERM6") (pin "1") (pinfunction "1_1") (pintype "passive"))
      (node (ref "U$12") (pin "1") (pinfunction "GND_1") (pintype "bidirectional"))
      (node (ref "U$12") (pin "5") (pinfunction "PG_5") (pintype "bidirectional"))
      (node (ref "U$12") (pin "P$2_GND") (pinfunction "GND_P$2_GND") (pintype "bidirectional"))
      (node (ref "U$12") (pin "P$3_GND") (pinfunction "GND_P$3_GND") (pintype "bidirectional"))
      (node (ref "U$12") (pin "THERMAL_GND") (pinfunction "GND_THERMAL_GND") (pintype "bidirectional"))
      (node (ref "U$57") (pin "GND1") (pinfunction "GND1_GND1") (pintype "bidirectional"))
      (node (ref "U$57") (pin "GND2") (pinfunction "GND2_GND2") (pintype "bidirectional"))
      (node (ref "U$57") (pin "GND3") (pinfunction "GND3_GND3") (pintype "bidirectional"))
      (node (ref "U$6") (pin "10") (pinfunction "PIN10(GND)_10") (pintype "bidirectional"))
      (node (ref "U$6") (pin "15") (pinfunction "PIN15(GND)_15") (pintype "bidirectional"))
      (node (ref "U$6") (pin "16") (pinfunction "PIN16(GND)_16") (pintype "bidirectional"))
      (node (ref "U$6") (pin "17") (pinfunction "COM3/I2C_ADDR_17") (pintype "bidirectional"))
      (node (ref "U$6") (pin "18") (pinfunction "COM2(GND)_18") (pintype "bidirectional"))
      (node (ref "U$6") (pin "2") (pinfunction "GND_2") (pintype "power_in"))
      (node (ref "U$6") (pin "25") (pinfunction "GND_25") (pintype "power_in"))
      (node (ref "U1") (pin "11") (pinfunction "GND_11") (pintype "bidirectional"))
      (node (ref "U1") (pin "16") (pinfunction "NC_16") (pintype "bidirectional"))
      (node (ref "U1") (pin "17") (pinfunction "PGND_PAD_17") (pintype "bidirectional"))
      (node (ref "U1") (pin "3") (pinfunction "1_PGND_3") (pintype "bidirectional"))
      (node (ref "U1") (pin "4") (pinfunction "2_PGND_4") (pintype "bidirectional"))
      (node (ref "U1") (pin "5") (pinfunction "3_PGND_5") (pintype "bidirectional"))
      (node (ref "U1") (pin "8") (pinfunction "SYNC_8") (pintype "bidirectional"))
      (node (ref "U1") (pin "PAD_1") (pinfunction "PGND_PAD_PAD_1") (pintype "bidirectional"))
      (node (ref "U1") (pin "PAD_2") (pinfunction "PGND_PAD_PAD_2") (pintype "bidirectional"))
      (node (ref "U1") (pin "PAD_3") (pinfunction "PGND_PAD_PAD_3") (pintype "bidirectional"))
      (node (ref "U1") (pin "PAD_4") (pinfunction "PGND_PAD_PAD_4") (pintype "bidirectional"))
      (node (ref "U1") (pin "PAD_5") (pinfunction "PGND_PAD_PAD_5") (pintype "bidirectional"))
      (node (ref "U1") (pin "PAD_6") (pinfunction "PGND_PAD_PAD_6") (pintype "bidirectional"))
      (node (ref "U16") (pin "P$10") (pinfunction "VSS1_P$10") (pintype "bidirectional"))
      (node (ref "U16") (pin "P$11") (pinfunction "VSS2_P$11") (pintype "bidirectional"))
      (node (ref "U16") (pin "P$21") (pinfunction "THERMAL_P$21") (pintype "bidirectional"))
      (node (ref "U3") (pin "10") (pinfunction "PGND2_10") (pintype "power_in"))
      (node (ref "U3") (pin "18") (pinfunction "GND_18") (pintype "power_in"))
      (node (ref "U3") (pin "3") (pinfunction "PGND1_3") (pintype "power_in"))
      (node (ref "U3") (pin "4") (pinfunction "PGND1_4") (pintype "power_in"))
      (node (ref "U3") (pin "9") (pinfunction "PGND2_9") (pintype "power_in"))
      (node (ref "U5") (pin "1") (pinfunction "A0_1") (pintype "bidirectional"))
      (node (ref "U5") (pin "12") (pinfunction "GND_12") (pintype "bidirectional"))
      (node (ref "U5") (pin "2") (pinfunction "A1_2") (pintype "bidirectional"))
      (node (ref "U5") (pin "21") (pinfunction "A2_21") (pintype "bidirectional"))
    )
    (net (code "12") (name "I2CMUX_~{RST}") (class "Default")
      (node (ref "R49") (pin "1") (pinfunction "1_1") (pintype "passive"))
      (node (ref "U$57") (pin "17-A3/TX4/SDA1") (pinfunction "17-A3/TX4/SDA1_17-A3/TX4/SDA1") (pintype "bidirectional"))
      (node (ref "U5") (pin "3") (pinfunction "~{RST}_3") (pintype "bidirectional"))
    )
    (net (code "13") (name "IMU_NRESET_3V") (class "Default")
      (node (ref "D1") (pin "A") (pinfunction "A_A") (pintype "passive"))
      (node (ref "R4") (pin "2") (pinfunction "2_2") (pintype "passive"))
      (node (ref "U$6") (pin "11") (pinfunction "NRESET_11") (pintype "bidirectional"))
    )
    (net (code "14") (name "IMU_RESET") (class "Default")
      (node (ref "D1") (pin "C") (pinfunction "C_C") (pintype "passive"))
      (node (ref "U$57") (pin "16-A2/RX4/SCL1") (pinfunction "16-A2/RX4/SCL1_16-A2/RX4/SCL1") (pintype "bidirectional"))
    )
    (net (code "15") (name "INT_3V") (class "Default")
      (node (ref "U$6") (pin "14") (pinfunction "INT_14") (pintype "output"))
    )
    (net (code "16") (name "LBO") (class "Default")
      (node (ref "T1") (pin "B") (pinfunction "B_B") (pintype "passive"))
      (node (ref "U1") (pin "10") (pinfunction "LBO_10") (pintype "bidirectional"))
    )
    (net (code "17") (name "LMIN1") (class "Default")
      (node (ref "U$57") (pin "7-RX2/OUT1A") (pinfunction "7-OUT1A/RX2_7-RX2/OUT1A") (pintype "bidirectional"))
      (node (ref "U3") (pin "17") (pinfunction "BIN1_17") (pintype "input"))
    )
    (net (code "18") (name "LMIN2") (class "Default")
      (node (ref "U$57") (pin "8-TX2/IN1") (pinfunction "8-IN1/TX2_8-TX2/IN1") (pintype "bidirectional"))
      (node (ref "U3") (pin "16") (pinfunction "BIN2_16") (pintype "input"))
    )
    (net (code "19") (name "LMOUT+") (class "Default")
      (node (ref "MOTORL") (pin "1") (pinfunction "1_1") (pintype "passive"))
      (node (ref "U3") (pin "11") (pinfunction "BOUT1_11") (pintype "output"))
      (node (ref "U3") (pin "12") (pinfunction "BOUT1_12") (pintype "output"))
    )
    (net (code "20") (name "LMOUT-") (class "Default")
      (node (ref "MOTORL") (pin "6") (pinfunction "6_6") (pintype "passive"))
      (node (ref "U3") (pin "7") (pinfunction "BOUT2_7") (pintype "output"))
      (node (ref "U3") (pin "8") (pinfunction "BOUT2_8") (pintype "output"))
    )
    (net (code "21") (name "Net-(C8-P$2)") (class "Default")
      (node (ref "C8") (pin "2") (pinfunction "P$2_2") (pintype "passive"))
      (node (ref "R14") (pin "2") (pinfunction "2_2") (pintype "passive"))
      (node (ref "R15") (pin "1") (pinfunction "1_1") (pintype "passive"))
      (node (ref "U$12") (pin "3") (pinfunction "FB_3") (pintype "bidirectional"))
    )
    (net (code "22") (name "Net-(CHRG-PadC)") (class "Default")
      (node (ref "CHRG") (pin "C") (pinfunction "C_C") (pintype "passive"))
      (node (ref "R121") (pin "2") (pinfunction "2_2") (pintype "passive"))
    )
    (net (code "23") (name "Net-(DONE-PadC)") (class "Default")
      (node (ref "DONE") (pin "C") (pinfunction "C_C") (pintype "passive"))
      (node (ref "R122") (pin "2") (pinfunction "2_2") (pintype "passive"))
    )
    (net (code "24") (name "Net-(L2-2)") (class "Default")
      (node (ref "L2") (pin "P$2") (pinfunction "2_P$2") (pintype "passive"))
      (node (ref "U$12") (pin "7") (pinfunction "SW_7") (pintype "bidirectional"))
    )
    (net (code "25") (name "Net-(L3-2)") (class "Default")
      (node (ref "L3") (pin "P$2") (pinfunction "2_P$2") (pintype "passive"))
      (node (ref "U1") (pin "1") (pinfunction "1_SW_1") (pintype "bidirectional"))
      (node (ref "U1") (pin "2") (pinfunction "2_SW_2") (pintype "bidirectional"))
    )
    (net (code "26") (name "Net-(LBO-PadA)") (class "Default")
      (node (ref "LBO") (pin "A") (pinfunction "A_A") (pintype "passive"))
      (node (ref "R21") (pin "1") (pinfunction "1_1") (pintype "passive"))
    )
    (net (code "27") (name "Net-(PWR-PadA)") (class "Default")
      (node (ref "PWR") (pin "A") (pinfunction "A_A") (pintype "passive"))
      (node (ref "R22") (pin "2") (pinfunction "2_2") (pintype "passive"))
    )
    (net (code "28") (name "Net-(R21-Pad2)") (class "Default")
      (node (ref "R21") (pin "2") (pinfunction "2_2") (pintype "passive"))
      (node (ref "T1") (pin "C") (pinfunction "C_C") (pintype "passive"))
    )
    (net (code "29") (name "Net-(R50-Pad2)") (class "Default")
      (node (ref "R50") (pin "2") (pinfunction "2_2") (pintype "passive"))
      (node (ref "TEENSY_POWER") (pin "C") (pinfunction "C_C") (pintype "passive"))
    )
    (net (code "30") (name "Net-(U$6-CAP)") (class "Default")
      (node (ref "C4") (pin "2") (pinfunction "2_2") (pintype "passive"))
      (node (ref "U$6") (pin "9") (pinfunction "CAP_9") (pintype "passive"))
    )
    (net (code "31") (name "Net-(U$6-XIN32)") (class "Default")
      (node (ref "C1") (pin "2") (pinfunction "2_2") (pintype "passive"))
      (node (ref "U$6") (pin "27") (pinfunction "XIN32_27") (pintype "input"))
      (node (ref "X2") (pin "P$2") (pinfunction "P$2_P$2") (pintype "bidirectional"))
    )
    (net (code "32") (name "Net-(U$6-XOUT32)") (class "Default")
      (node (ref "C2") (pin "2") (pinfunction "2_2") (pintype "passive"))
      (node (ref "U$6") (pin "26") (pinfunction "XOUT32_26") (pintype "output"))
      (node (ref "X2") (pin "P$1") (pinfunction "P$1_P$1") (pintype "bidirectional"))
    )
    (net (code "33") (name "Net-(U1-FB)") (class "Default")
      (node (ref "R24") (pin "1") (pinfunction "1_1") (pintype "passive"))
      (node (ref "R25") (pin "2") (pinfunction "2_2") (pintype "passive"))
      (node (ref "U1") (pin "12") (pinfunction "FB_12") (pintype "bidirectional"))
    )
    (net (code "34") (name "Net-(U1-LBI)") (class "Default")
      (node (ref "R26") (pin "2") (pinfunction "2_2") (pintype "passive"))
      (node (ref "R27") (pin "1") (pinfunction "1_1") (pintype "passive"))
      (node (ref "U1") (pin "7") (pinfunction "LBI_7") (pintype "bidirectional"))
    )
    (net (code "35") (name "Net-(U16-PROG1)") (class "Default")
      (node (ref "R123") (pin "2") (pinfunction "2_2") (pintype "passive"))
      (node (ref "U16") (pin "P$13") (pinfunction "PROG1_P$13") (pintype "bidirectional"))
    )
    (net (code "36") (name "Net-(U16-PROG3)") (class "Default")
      (node (ref "R124") (pin "2") (pinfunction "2_2") (pintype "passive"))
      (node (ref "U16") (pin "P$12") (pinfunction "PROG3_P$12") (pintype "bidirectional"))
    )
    (net (code "37") (name "Net-(U16-STAT1{slash}LBO)") (class "Default")
      (node (ref "R121") (pin "1") (pinfunction "1_1") (pintype "passive"))
      (node (ref "U16") (pin "P$8") (pinfunction "STAT1/LBO_P$8") (pintype "bidirectional"))
    )
    (net (code "38") (name "Net-(U16-STAT2)") (class "Default")
      (node (ref "R122") (pin "1") (pinfunction "1_1") (pintype "passive"))
      (node (ref "U16") (pin "P$7") (pinfunction "STAT2_P$7") (pintype "bidirectional"))
    )
    (net (code "39") (name "Net-(U16-THERM)") (class "Default")
      (node (ref "THERM6") (pin "2") (pinfunction "2_2") (pintype "passive"))
      (node (ref "U16") (pin "P$5") (pinfunction "THERM_P$5") (pintype "bidirectional"))
    )
    (net (code "40") (name "Net-(U16-VPCC)") (class "Default")
      (node (ref "R119") (pin "1") (pinfunction "1_1") (pintype "passive"))
      (node (ref "R120") (pin "1") (pinfunction "1_1") (pintype "passive"))
      (node (ref "U16") (pin "P$2") (pinfunction "VPCC_P$2") (pintype "bidirectional"))
    )
    (net (code "41") (name "PS0_3V") (class "Default")
      (node (ref "R3") (pin "3") (pinfunction "1_3") (pintype "passive"))
      (node (ref "U$6") (pin "6") (pinfunction "PS0_6") (pintype "input"))
    )
    (net (code "42") (name "PS1_3V") (class "Default")
      (node (ref "R3") (pin "4") (pinfunction "1_4") (pintype "passive"))
      (node (ref "U$6") (pin "5") (pinfunction "PS1_5") (pintype "input"))
    )
    (net (code "43") (name "PWML") (class "Default")
      (node (ref "U$57") (pin "23-A9/CRX1/CCLK1") (pinfunction "23-A9/CRX1/MCLK1_23-A9/CRX1/CCLK1") (pintype "bidirectional"))
      (node (ref "U3") (pin "15") (pinfunction "PWMB_15") (pintype "input"))
    )
    (net (code "44") (name "PWMR") (class "Default")
      (node (ref "U$57") (pin "4-BCLK2") (pinfunction "4-BCLK1_4-BCLK2") (pintype "bidirectional"))
      (node (ref "U3") (pin "23") (pinfunction "PWMA_23") (pintype "input"))
    )
    (net (code "45") (name "RMIN1") (class "Default")
      (node (ref "U$57") (pin "0-RX1") (pinfunction "0-RX1/CRX2_0-RX1") (pintype "bidirectional"))
      (node (ref "U3") (pin "21") (pinfunction "AIN1_21") (pintype "input"))
    )
    (net (code "46") (name "RMIN2") (class "Default")
      (node (ref "U$57") (pin "1-TX1") (pinfunction "1-TX1/CTX2_1-TX1") (pintype "bidirectional"))
      (node (ref "U3") (pin "22") (pinfunction "AIN2_22") (pintype "input"))
    )
    (net (code "47") (name "RMOUT+") (class "Default")
      (node (ref "MOTORR") (pin "1") (pinfunction "1_1") (pintype "passive"))
      (node (ref "U3") (pin "1") (pinfunction "AOUT1_1") (pintype "output"))
      (node (ref "U3") (pin "2") (pinfunction "AOUT1_2") (pintype "output"))
    )
    (net (code "48") (name "RMOUT-") (class "Default")
      (node (ref "MOTORR") (pin "6") (pinfunction "6_6") (pintype "passive"))
      (node (ref "U3") (pin "5") (pinfunction "AOUT2_5") (pintype "output"))
      (node (ref "U3") (pin "6") (pinfunction "AOUT2_6") (pintype "output"))
    )
    (net (code "49") (name "RPI_RX") (class "Default")
      (node (ref "J4") (pin "1") (pinfunction "1_1") (pintype "passive"))
      (node (ref "U$57") (pin "14-A0/TX3/S-PFI_OUT") (pinfunction "14-A0/TX3/S-PDIF_IN_14-A0/TX3/S-PFI_OUT") (pintype "bidirectional"))
    )
    (net (code "50") (name "RPI_TX") (class "Default")
      (node (ref "J4") (pin "2") (pinfunction "2_2") (pintype "passive"))
      (node (ref "U$57") (pin "15-A1/RX3/S-PDIF_IN") (pinfunction "15-A1/RX3/SPDIF_IN_15-A1/RX3/S-PDIF_IN") (pintype "bidirectional"))
    )
    (net (code "51") (name "SCL0") (class "Default")
      (node (ref "JD0") (pin "4") (pinfunction "4_4") (pintype "passive"))
      (node (ref "R29") (pin "2") (pinfunction "2_2") (pintype "passive"))
      (node (ref "U5") (pin "5") (pinfunction "SC0_5") (pintype "bidirectional"))
    )
    (net (code "52") (name "SCL1") (class "Default")
      (node (ref "JD1") (pin "4") (pinfunction "4_4") (pintype "passive"))
      (node (ref "R31") (pin "2") (pinfunction "2_2") (pintype "passive"))
      (node (ref "U5") (pin "7") (pinfunction "SC1_7") (pintype "bidirectional"))
    )
    (net (code "53") (name "SCL2") (class "Default")
      (node (ref "JD2") (pin "4") (pinfunction "4_4") (pintype "passive"))
      (node (ref "R33") (pin "2") (pinfunction "2_2") (pintype "passive"))
      (node (ref "U5") (pin "9") (pinfunction "SC2_9") (pintype "bidirectional"))
    )
    (net (code "54") (name "SCL3") (class "Default")
      (node (ref "JD3") (pin "4") (pinfunction "4_4") (pintype "passive"))
      (node (ref "R35") (pin "2") (pinfunction "2_2") (pintype "passive"))
      (node (ref "U5") (pin "11") (pinfunction "SC3_11") (pintype "bidirectional"))
    )
    (net (code "55") (name "SCL4") (class "Default")
      (node (ref "JD4") (pin "4") (pinfunction "4_4") (pintype "passive"))
      (node (ref "R37") (pin "2") (pinfunction "2_2") (pintype "passive"))
      (node (ref "U5") (pin "14") (pinfunction "SC4_14") (pintype "bidirectional"))
    )
    (net (code "56") (name "SCL5") (class "Default")
      (node (ref "JD5") (pin "4") (pinfunction "4_4") (pintype "passive"))
      (node (ref "R39") (pin "2") (pinfunction "2_2") (pintype "passive"))
      (node (ref "U5") (pin "16") (pinfunction "SC5_16") (pintype "bidirectional"))
    )
    (net (code "57") (name "SCL6") (class "Default")
      (node (ref "JD6") (pin "4") (pinfunction "4_4") (pintype "passive"))
      (node (ref "R41") (pin "2") (pinfunction "2_2") (pintype "passive"))
      (node (ref "U5") (pin "18") (pinfunction "SC6_18") (pintype "bidirectional"))
    )
    (net (code "58") (name "SCL_MAIN") (class "Default")
      (node (ref "IC1") (pin "9") (pinfunction "SCL_9") (pintype "bidirectional"))
      (node (ref "R9") (pin "8") (pinfunction "2_8") (pintype "passive"))
      (node (ref "U$57") (pin "19-A5/SCL0") (pinfunction "19-A5/SCL0_19-A5/SCL0") (pintype "bidirectional"))
      (node (ref "U$6") (pin "19") (pinfunction "COM1/SCL/RX_19") (pintype "bidirectional"))
      (node (ref "U5") (pin "22") (pinfunction "SCL_22") (pintype "bidirectional"))
    )
    (net (code "59") (name "SDA0") (class "Default")
      (node (ref "JD0") (pin "3") (pinfunction "3_3") (pintype "passive"))
      (node (ref "R28") (pin "2") (pinfunction "2_2") (pintype "passive"))
      (node (ref "U5") (pin "4") (pinfunction "SD0_4") (pintype "bidirectional"))
    )
    (net (code "60") (name "SDA1") (class "Default")
      (node (ref "JD1") (pin "3") (pinfunction "3_3") (pintype "passive"))
      (node (ref "R30") (pin "2") (pinfunction "2_2") (pintype "passive"))
      (node (ref "U5") (pin "6") (pinfunction "SD1_6") (pintype "bidirectional"))
    )
    (net (code "61") (name "SDA2") (class "Default")
      (node (ref "JD2") (pin "3") (pinfunction "3_3") (pintype "passive"))
      (node (ref "R32") (pin "2") (pinfunction "2_2") (pintype "passive"))
      (node (ref "U5") (pin "8") (pinfunction "SD2_8") (pintype "bidirectional"))
    )
    (net (code "62") (name "SDA3") (class "Default")
      (node (ref "JD3") (pin "3") (pinfunction "3_3") (pintype "passive"))
      (node (ref "R34") (pin "2") (pinfunction "2_2") (pintype "passive"))
      (node (ref "U5") (pin "10") (pinfunction "SD3_10") (pintype "bidirectional"))
    )
    (net (code "63") (name "SDA4") (class "Default")
      (node (ref "JD4") (pin "3") (pinfunction "3_3") (pintype "passive"))
      (node (ref "R36") (pin "2") (pinfunction "2_2") (pintype "passive"))
      (node (ref "U5") (pin "13") (pinfunction "SD4_13") (pintype "bidirectional"))
    )
    (net (code "64") (name "SDA5") (class "Default")
      (node (ref "JD5") (pin "3") (pinfunction "3_3") (pintype "passive"))
      (node (ref "R38") (pin "2") (pinfunction "2_2") (pintype "passive"))
      (node (ref "U5") (pin "15") (pinfunction "SD5_15") (pintype "bidirectional"))
    )
    (net (code "65") (name "SDA6") (class "Default")
      (node (ref "JD6") (pin "3") (pinfunction "3_3") (pintype "passive"))
      (node (ref "R40") (pin "2") (pinfunction "2_2") (pintype "passive"))
      (node (ref "U5") (pin "17") (pinfunction "SD6_17") (pintype "bidirectional"))
    )
    (net (code "66") (name "SDA_MAIN") (class "Default")
      (node (ref "IC1") (pin "8") (pinfunction "SDA_8") (pintype "bidirectional"))
      (node (ref "R9") (pin "5") (pinfunction "2_5") (pintype "passive"))
      (node (ref "U$57") (pin "18-A4/SDA0") (pinfunction "18-A4/SDA0_18-A4/SDA0") (pintype "bidirectional"))
      (node (ref "U$6") (pin "20") (pinfunction "COM0/SDA/TX_20") (pintype "bidirectional"))
      (node (ref "U5") (pin "23") (pinfunction "SDA_23") (pintype "bidirectional"))
    )
    (net (code "67") (name "STBY") (class "Default")
      (node (ref "R16") (pin "1") (pinfunction "1_1") (pintype "passive"))
      (node (ref "U3") (pin "19") (pinfunction "STBY_19") (pintype "input"))
    )
    (net (code "68") (name "VBAT") (class "Default")
      (node (ref "C13") (pin "1") (pinfunction "1_1") (pintype "passive"))
      (node (ref "C15") (pin "1") (pinfunction "1_1") (pintype "passive"))
      (node (ref "C3") (pin "1") (pinfunction "P$1_1") (pintype "passive"))
      (node (ref "C7") (pin "1") (pinfunction "P$1_1") (pintype "passive"))
      (node (ref "IC1") (pin "14") (pinfunction "IN-_14") (pintype "bidirectional"))
      (node (ref "IC1") (pin "15") (pinfunction "IN-_15") (pintype "bidirectional"))
      (node (ref "IC1") (pin "16") (pinfunction "IN-_16") (pintype "bidirectional"))
      (node (ref "JP1") (pin "2") (pinfunction "2_2") (pintype "passive"))
      (node (ref "L2") (pin "P$1") (pinfunction "1_P$1") (pintype "passive"))
      (node (ref "L3") (pin "P$1") (pinfunction "1_P$1") (pintype "passive"))
      (node (ref "R1") (pin "1") (pinfunction "1_1") (pintype "passive"))
      (node (ref "R11") (pin "2") (pinfunction "2_2") (pintype "passive"))
      (node (ref "R27") (pin "2") (pinfunction "2_2") (pintype "passive"))
      (node (ref "T1") (pin "E") (pinfunction "E_E") (pintype "passive"))
      (node (ref "U$12") (pin "4") (pinfunction "ILIM_4") (pintype "bidirectional"))
      (node (ref "U$12") (pin "8") (pinfunction "VIN_8") (pintype "bidirectional"))
      (node (ref "U1") (pin "6") (pinfunction "VBAT_6") (pintype "bidirectional"))
    )
    (net (code "69") (name "VBAT_IN") (class "Default")
      (node (ref "IC1") (pin "1") (pinfunction "IN+_1") (pintype "bidirectional"))
      (node (ref "IC1") (pin "12") (pinfunction "VBUS_12") (pintype "power_in"))
      (node (ref "IC1") (pin "2") (pinfunction "IN+_2") (pintype "bidirectional"))
      (node (ref "IC1") (pin "3") (pinfunction "IN+_3") (pintype "bidirectional"))
      (node (ref "JP1") (pin "1") (pinfunction "1_1") (pintype "passive"))
      (node (ref "U16") (pin "P$1") (pinfunction "VOUT1_P$1") (pintype "bidirectional"))
      (node (ref "U16") (pin "P$20") (pinfunction "VOUT2_P$20") (pintype "bidirectional"))
    )
    (net (code "70") (name "VBAT_MEASURE") (class "Default")
      (node (ref "R11") (pin "1") (pinfunction "1_1") (pintype "passive"))
      (node (ref "R12") (pin "2") (pinfunction "2_2") (pintype "passive"))
      (node (ref "U$57") (pin "22-A8/CTX1") (pinfunction "22-A8/CTX1_22-A8/CTX1") (pintype "bidirectional"))
    )
    (net (code "71") (name "VBUS") (class "Default")
      (node (ref "C17") (pin "1") (pinfunction "1_1") (pintype "passive"))
      (node (ref "CHRG") (pin "A") (pinfunction "A_A") (pintype "passive"))
      (node (ref "CN4") (pin "VBUS") (pinfunction "VBUS_VBUS") (pintype "power_in"))
      (node (ref "DONE") (pin "A") (pinfunction "A_A") (pintype "passive"))
      (node (ref "R119") (pin "2") (pinfunction "2_2") (pintype "passive"))
      (node (ref "R13") (pin "1") (pinfunction "1_1") (pintype "passive"))
      (node (ref "U16") (pin "P$17") (pinfunction "CE_P$17") (pintype "bidirectional"))
      (node (ref "U16") (pin "P$18") (pinfunction "VIN1_P$18") (pintype "bidirectional"))
      (node (ref "U16") (pin "P$19") (pinfunction "VIN2_P$19") (pintype "bidirectional"))
      (node (ref "U16") (pin "P$3") (pinfunction "SEL_P$3") (pintype "bidirectional"))
      (node (ref "U16") (pin "P$4") (pinfunction "PROG2_P$4") (pintype "bidirectional"))
      (node (ref "U16") (pin "P$9") (pinfunction "/TE_P$9") (pintype "bidirectional"))
    )
    (net (code "72") (name "VLIPO") (class "Default")
      (node (ref "B1") (pin "2") (pinfunction "+_2") (pintype "passive"))
      (node (ref "C49") (pin "1") (pinfunction "1_1") (pintype "passive"))
      (node (ref "U16") (pin "P$14") (pinfunction "VBAT1_P$14") (pintype "bidirectional"))
      (node (ref "U16") (pin "P$15") (pinfunction "VBAT2_P$15") (pintype "bidirectional"))
      (node (ref "U16") (pin "P$16") (pinfunction "VBATSENS_P$16") (pintype "bidirectional"))
    )
    (net (code "73") (name "VMOTOR") (class "Default")
      (node (ref "C11") (pin "1") (pinfunction "P$1_1") (pintype "passive"))
      (node (ref "Q2") (pin "2") (pinfunction "S_2") (pintype "passive"))
      (node (ref "U3") (pin "13") (pinfunction "VM_13") (pintype "power_in"))
      (node (ref "U3") (pin "14") (pinfunction "VM_14") (pintype "power_in"))
      (node (ref "U3") (pin "24") (pinfunction "VM_24") (pintype "power_in"))
    )
    (net (code "74") (name "unconnected-(CN4-PadD+)") (class "Default")
      (node (ref "CN4") (pin "D+") (pinfunction "D+_D+") (pintype "bidirectional"))
    )
    (net (code "75") (name "unconnected-(CN4-PadD-)") (class "Default")
      (node (ref "CN4") (pin "D-") (pinfunction "D-_D-") (pintype "bidirectional"))
    )
    (net (code "76") (name "unconnected-(CN4-PadID)") (class "Default")
      (node (ref "CN4") (pin "ID") (pinfunction "ID_ID") (pintype "bidirectional"))
    )
    (net (code "77") (name "unconnected-(S1-NC-Pad1)") (class "Default")
      (node (ref "S1") (pin "1") (pinfunction "NC_1") (pintype "no_connect"))
    )
    (net (code "78") (name "unconnected-(U$6-PIN7(SWDIO)-Pad7)") (class "Default")
      (node (ref "U$6") (pin "7") (pinfunction "PIN7(SWDIO)_7") (pintype "bidirectional"))
    )
    (net (code "79") (name "unconnected-(U$57-10-CS-Pad10-CS{slash}MQSR)") (class "Default")
      (node (ref "U$57") (pin "10-CS/MQSR") (pinfunction "10-CS_10-CS/MQSR") (pintype "bidirectional"))
    )
    (net (code "80") (name "unconnected-(U$57-12-MISO{slash}MQSL-Pad12-MIO{slash}MQSL)") (class "Default")
      (node (ref "U$57") (pin "12-MIO/MQSL") (pinfunction "12-MISO/MQSL_12-MIO/MQSL") (pintype "bidirectional"))
    )
    (net (code "81") (name "unconnected-(U$57-25-A11{slash}RX6{slash}SDA2-Pad25-A11{slash}SDA2)") (class "Default")
      (node (ref "U$57") (pin "25-A11/SDA2") (pinfunction "25-A11/RX6/SDA2_25-A11/SDA2") (pintype "bidirectional"))
    )
    (net (code "82") (name "unconnected-(U$57-32-OUT1B-Pad32-OUTB1)") (class "Default")
      (node (ref "U$57") (pin "32-OUTB1") (pinfunction "32-OUT1B_32-OUTB1") (pintype "bidirectional"))
    )
    (net (code "83") (name "unconnected-(U$57-Pad3V3-2)") (class "Default")
      (node (ref "U$57") (pin "3V3-2") (pinfunction "3V3-2_3V3-2") (pintype "bidirectional"))
    )
    (net (code "84") (name "unconnected-(U$57-Pad5-IN2)") (class "Default")
      (node (ref "U$57") (pin "5-IN2") (pinfunction "5-IN2_5-IN2") (pintype "bidirectional"))
    )
    (net (code "85") (name "unconnected-(U$57-Pad6-OUT1D)") (class "Default")
      (node (ref "U$57") (pin "6-OUT1D") (pinfunction "6-OUT1D_6-OUT1D") (pintype "bidirectional"))
    )
    (net (code "86") (name "unconnected-(U$57-Pad9-OUT1C)") (class "Default")
      (node (ref "U$57") (pin "9-OUT1C") (pinfunction "9-OUT1C_9-OUT1C") (pintype "bidirectional"))
    )
    (net (code "87") (name "unconnected-(U$57-Pad11-MOSI{slash}CTX1)") (class "Default")
      (node (ref "U$57") (pin "11-MOSI/CTX1") (pinfunction "11-MOSI/CTX1_11-MOSI/CTX1") (pintype "bidirectional"))
    )
    (net (code "88") (name "unconnected-(U$57-Pad24-A10{slash}TX6{slash}SCL2)") (class "Default")
      (node (ref "U$57") (pin "24-A10/TX6/SCL2") (pinfunction "24-A10/TX6/SCL2_24-A10/TX6/SCL2") (pintype "bidirectional"))
    )
    (net (code "89") (name "unconnected-(U$57-Pad26-A12{slash}MOSI1)") (class "Default")
      (node (ref "U$57") (pin "26-A12/MOSI1") (pinfunction "26-A12/MOSI1_26-A12/MOSI1") (pintype "bidirectional"))
    )
    (net (code "90") (name "unconnected-(U$57-Pad27-A13{slash}SCK1)") (class "Default")
      (node (ref "U$57") (pin "27-A13/SCK1") (pinfunction "27-A13/SCK1_27-A13/SCK1") (pintype "bidirectional"))
    )
    (net (code "91") (name "unconnected-(U$57-Pad28-RX7)") (class "Default")
      (node (ref "U$57") (pin "28-RX7") (pinfunction "28-RX7_28-RX7") (pintype "bidirectional"))
    )
    (net (code "92") (name "unconnected-(U$57-Pad29-TX7)") (class "Default")
      (node (ref "U$57") (pin "29-TX7") (pinfunction "29-TX7_29-TX7") (pintype "bidirectional"))
    )
    (net (code "93") (name "unconnected-(U$57-Pad30-CRX3)") (class "Default")
      (node (ref "U$57") (pin "30-CRX3") (pinfunction "30-CRX3_30-CRX3") (pintype "bidirectional"))
    )
    (net (code "94") (name "unconnected-(U$57-Pad31-CTX3)") (class "Default")
      (node (ref "U$57") (pin "31-CTX3") (pinfunction "31-CTX3_31-CTX3") (pintype "bidirectional"))
    )
    (net (code "95") (name "unconnected-(U$57-Pad33-MCLK2)") (class "Default")
      (node (ref "U$57") (pin "33-MCLK2") (pinfunction "33-MCLK2_33-MCLK2") (pintype "bidirectional"))
    )
    (net (code "96") (name "unconnected-(U$57-PadON{slash}OFF)") (class "Default")
      (node (ref "U$57") (pin "ON/OFF") (pinfunction "ON/OFF_ON/OFF") (pintype "bidirectional"))
    )
    (net (code "97") (name "unconnected-(U$57-PadPROGRAM)") (class "Default")
      (node (ref "U$57") (pin "PROGRAM") (pinfunction "PROGRAM_PROGRAM") (pintype "bidirectional"))
    )
    (net (code "98") (name "unconnected-(U$57-PadVBAT)") (class "Default")
      (node (ref "U$57") (pin "VBAT") (pinfunction "VBAT_VBAT") (pintype "bidirectional"))
    )
    (net (code "99") (name "unconnected-(U$57-PadVUSB)") (class "Default")
      (node (ref "U$57") (pin "VUSB") (pinfunction "VUSB_VUSB") (pintype "bidirectional"))
    )
    (net (code "100") (name "unconnected-(U5-SC7-Pad20)") (class "Default")
      (node (ref "U5") (pin "20") (pinfunction "SC7_20") (pintype "bidirectional"))
    )
    (net (code "101") (name "unconnected-(U5-SD7-Pad19)") (class "Default")
      (node (ref "U5") (pin "19") (pinfunction "SD7_19") (pintype "bidirectional"))
    )
    (net (code "102") (name "unconnected-(U16-{slash}PG-PadP$6)") (class "Default")
      (node (ref "U16") (pin "P$6") (pinfunction "/PG_P$6") (pintype "bidirectional"))
    )
  )
)
